# Precision_Arduino_Charlieplex_1_1.net
KiCad netlist of a schematic drawn in EAGLE
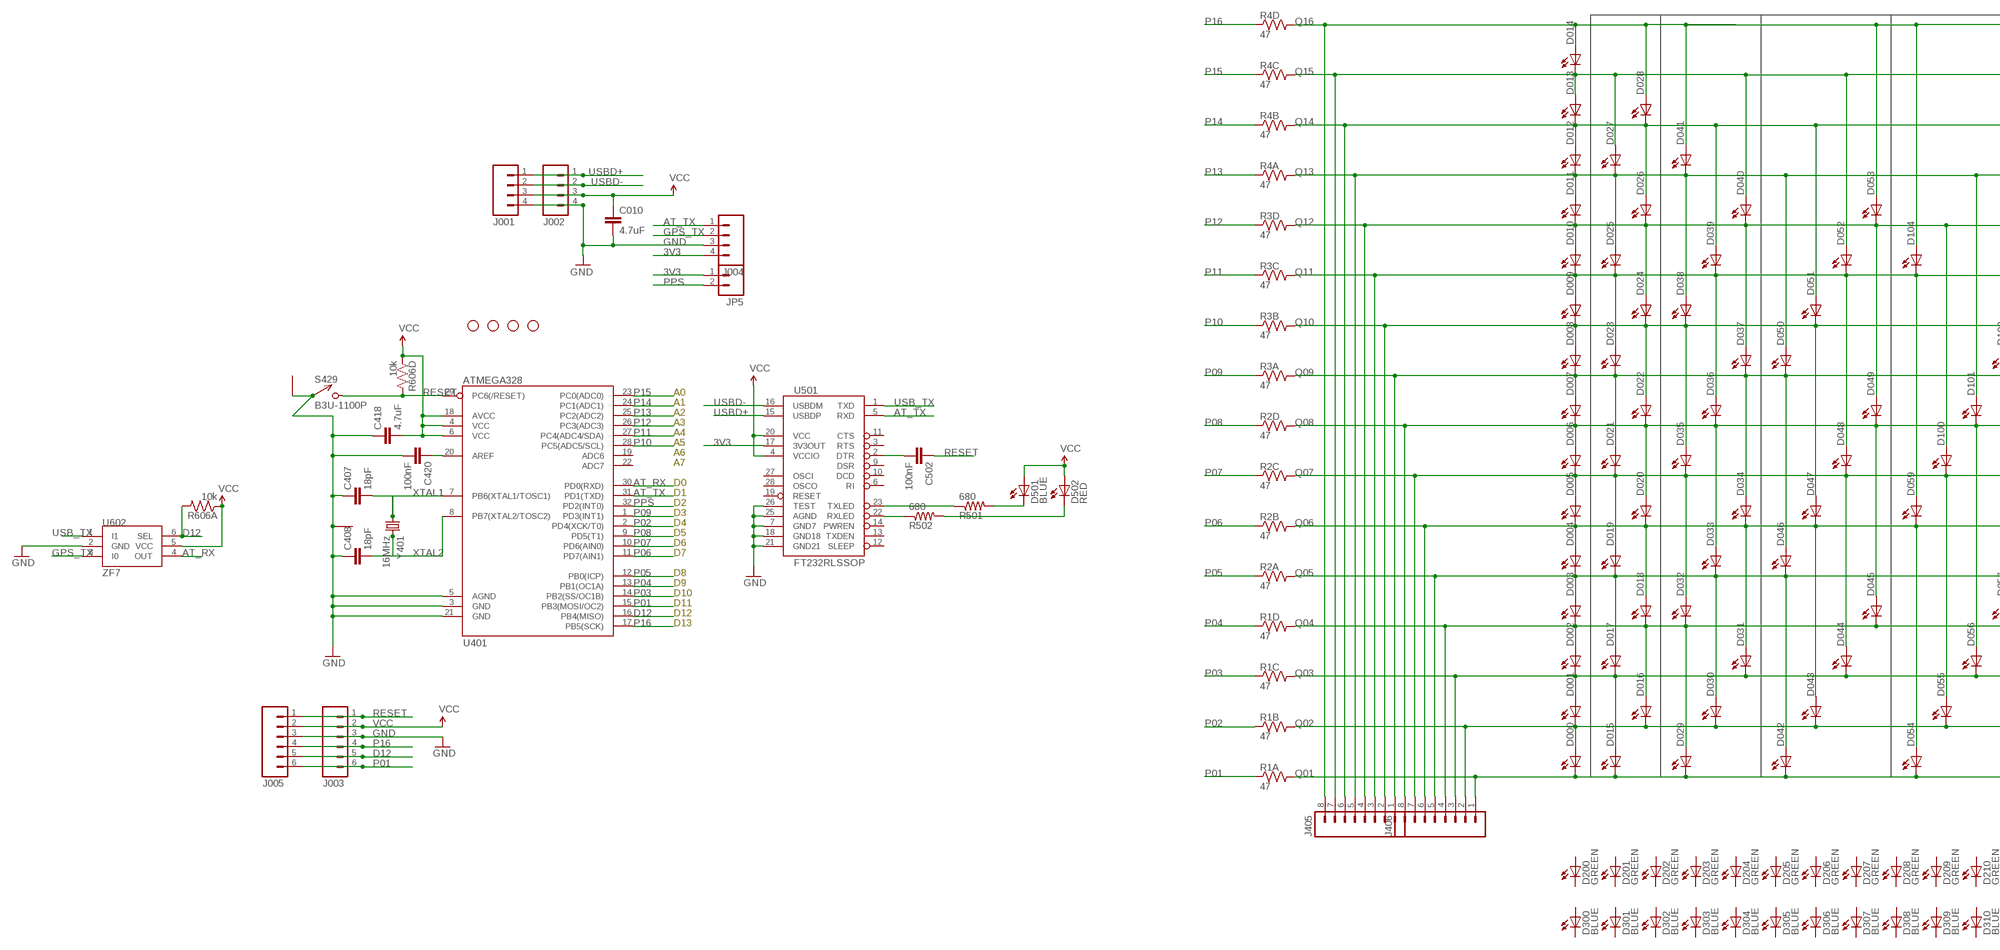
[diagram p0: schematic, sheet 1, part 1 of 2]
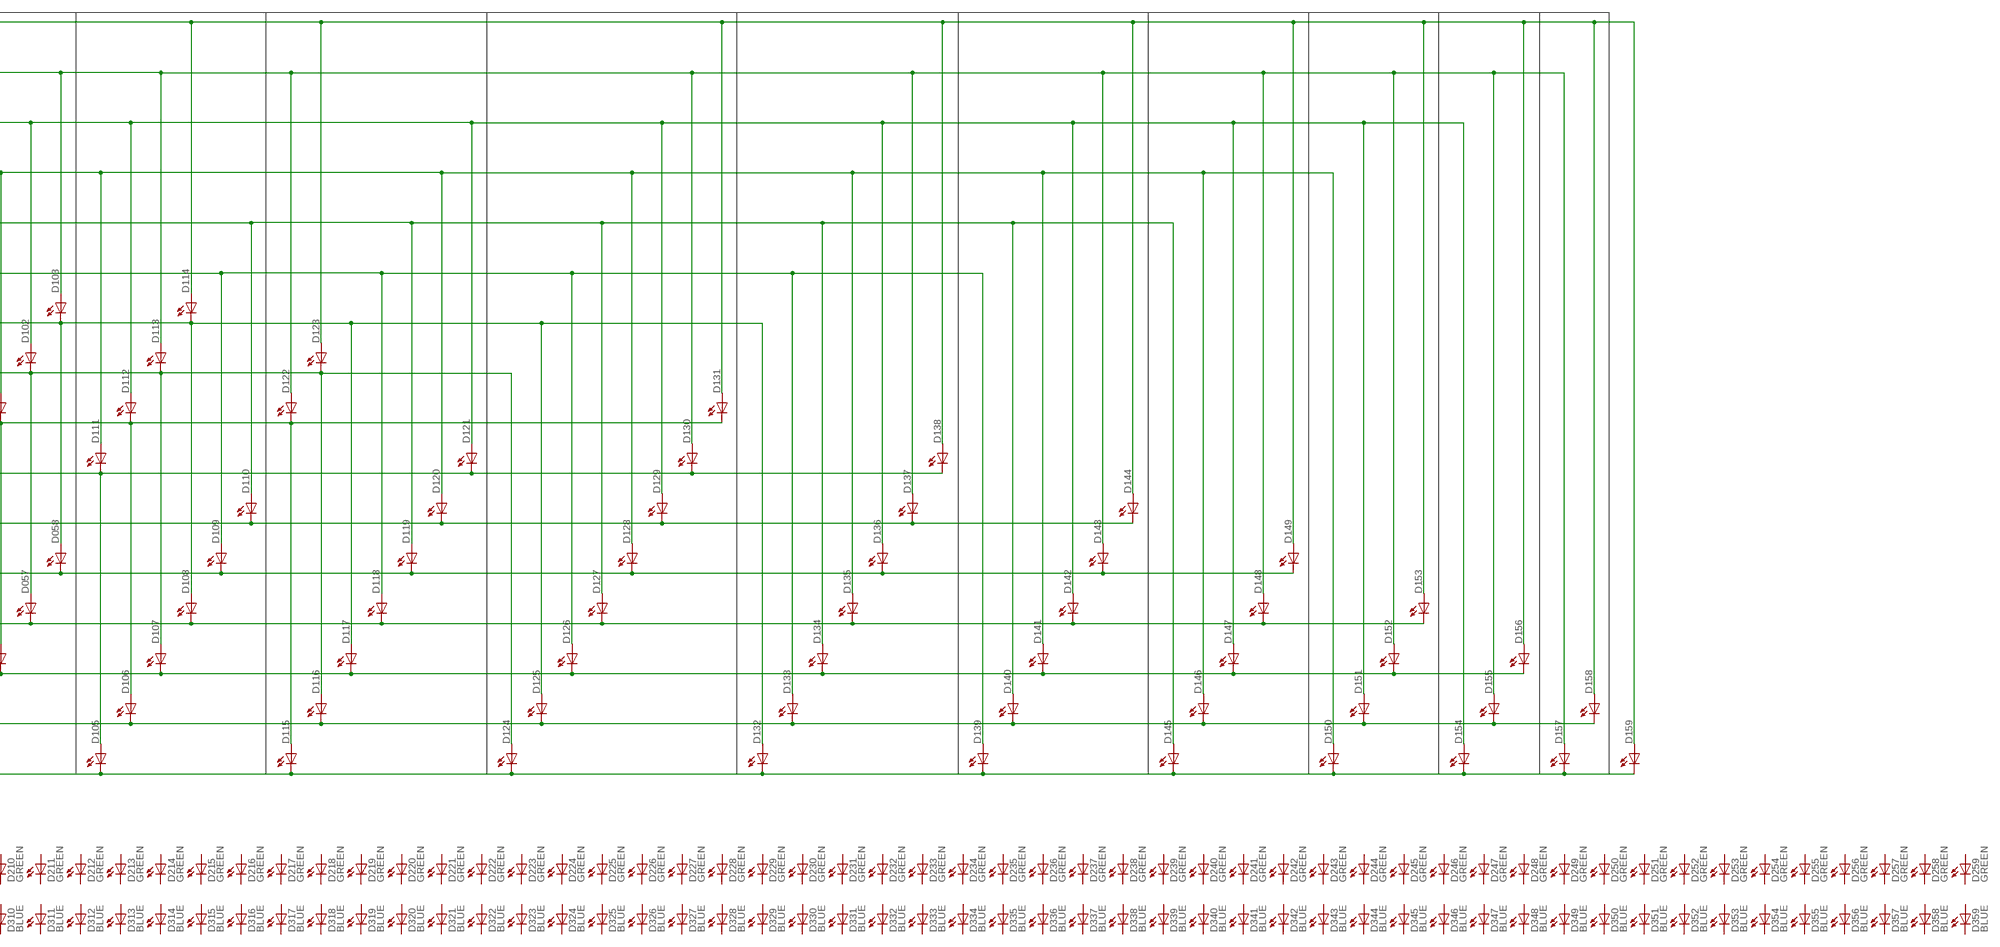
[diagram p1: schematic, sheet 1, part 2 of 2]

(export (version "E")
  (design (tool "Eeschema 10.0.6"))
  (components
    (comp (ref "C010")
      (value "4.7uF")
      (footprint "eagle-import:0603-CAP")
      (libsource (lib "eagle-import") (part "CAP0603-CAP"))
    )
    (comp (ref "C407")
      (value "18pF")
      (footprint "eagle-import:0603-CAP")
      (libsource (lib "eagle-import") (part "CAP0603-CAP"))
    )
    (comp (ref "C408")
      (value "18pF")
      (footprint "eagle-import:0603-CAP")
      (libsource (lib "eagle-import") (part "CAP0603-CAP"))
    )
    (comp (ref "C418")
      (value "4.7uF")
      (footprint "eagle-import:0603-CAP")
      (libsource (lib "eagle-import") (part "CAP0603-CAP"))
    )
    (comp (ref "C420")
      (value "100nF")
      (footprint "eagle-import:0603-CAP")
      (libsource (lib "eagle-import") (part "CAP0603-CAP"))
    )
    (comp (ref "C502")
      (value "100nF")
      (footprint "eagle-import:0603-CAP")
      (libsource (lib "eagle-import") (part "CAP0603-CAP"))
    )
    (comp (ref "D000")
      (value "RED")
      (footprint "eagle-import:LED-0603")
      (libsource (lib "eagle-import") (part "SparkFun-LED_LED0603"))
    )
    (comp (ref "D001")
      (value "RED")
      (footprint "eagle-import:LED-0603")
      (libsource (lib "eagle-import") (part "SparkFun-LED_LED0603"))
    )
    (comp (ref "D002")
      (value "RED")
      (footprint "eagle-import:LED-0603")
      (libsource (lib "eagle-import") (part "SparkFun-LED_LED0603"))
    )
    (comp (ref "D003")
      (value "RED")
      (footprint "eagle-import:LED-0603")
      (libsource (lib "eagle-import") (part "SparkFun-LED_LED0603"))
    )
    (comp (ref "D004")
      (value "RED")
      (footprint "eagle-import:LED-0603")
      (libsource (lib "eagle-import") (part "SparkFun-LED_LED0603"))
    )
    (comp (ref "D005")
      (value "RED")
      (footprint "eagle-import:LED-0603")
      (libsource (lib "eagle-import") (part "SparkFun-LED_LED0603"))
    )
    (comp (ref "D006")
      (value "RED")
      (footprint "eagle-import:LED-0603")
      (libsource (lib "eagle-import") (part "SparkFun-LED_LED0603"))
    )
    (comp (ref "D007")
      (value "RED")
      (footprint "eagle-import:LED-0603")
      (libsource (lib "eagle-import") (part "SparkFun-LED_LED0603"))
    )
    (comp (ref "D008")
      (value "RED")
      (footprint "eagle-import:LED-0603")
      (libsource (lib "eagle-import") (part "SparkFun-LED_LED0603"))
    )
    (comp (ref "D009")
      (value "RED")
      (footprint "eagle-import:LED-0603")
      (libsource (lib "eagle-import") (part "SparkFun-LED_LED0603"))
    )
    (comp (ref "D010")
      (value "RED")
      (footprint "eagle-import:LED-0603")
      (libsource (lib "eagle-import") (part "SparkFun-LED_LED0603"))
    )
    (comp (ref "D011")
      (value "RED")
      (footprint "eagle-import:LED-0603")
      (libsource (lib "eagle-import") (part "SparkFun-LED_LED0603"))
    )
    (comp (ref "D012")
      (value "RED")
      (footprint "eagle-import:LED-0603")
      (libsource (lib "eagle-import") (part "SparkFun-LED_LED0603"))
    )
    (comp (ref "D013")
      (value "RED")
      (footprint "eagle-import:LED-0603")
      (libsource (lib "eagle-import") (part "SparkFun-LED_LED0603"))
    )
    (comp (ref "D014")
      (value "RED")
      (footprint "eagle-import:LED-0603")
      (libsource (lib "eagle-import") (part "SparkFun-LED_LED0603"))
    )
    (comp (ref "D015")
      (value "RED")
      (footprint "eagle-import:LED-0603")
      (libsource (lib "eagle-import") (part "SparkFun-LED_LED0603"))
    )
    (comp (ref "D016")
      (value "RED")
      (footprint "eagle-import:LED-0603")
      (libsource (lib "eagle-import") (part "SparkFun-LED_LED0603"))
    )
    (comp (ref "D017")
      (value "RED")
      (footprint "eagle-import:LED-0603")
      (libsource (lib "eagle-import") (part "SparkFun-LED_LED0603"))
    )
    (comp (ref "D018")
      (value "RED")
      (footprint "eagle-import:LED-0603")
      (libsource (lib "eagle-import") (part "SparkFun-LED_LED0603"))
    )
    (comp (ref "D019")
      (value "RED")
      (footprint "eagle-import:LED-0603")
      (libsource (lib "eagle-import") (part "SparkFun-LED_LED0603"))
    )
    (comp (ref "D020")
      (value "RED")
      (footprint "eagle-import:LED-0603")
      (libsource (lib "eagle-import") (part "SparkFun-LED_LED0603"))
    )
    (comp (ref "D021")
      (value "RED")
      (footprint "eagle-import:LED-0603")
      (libsource (lib "eagle-import") (part "SparkFun-LED_LED0603"))
    )
    (comp (ref "D022")
      (value "RED")
      (footprint "eagle-import:LED-0603")
      (libsource (lib "eagle-import") (part "SparkFun-LED_LED0603"))
    )
    (comp (ref "D023")
      (value "RED")
      (footprint "eagle-import:LED-0603")
      (libsource (lib "eagle-import") (part "SparkFun-LED_LED0603"))
    )
    (comp (ref "D024")
      (value "RED")
      (footprint "eagle-import:LED-0603")
      (libsource (lib "eagle-import") (part "SparkFun-LED_LED0603"))
    )
    (comp (ref "D025")
      (value "RED")
      (footprint "eagle-import:LED-0603")
      (libsource (lib "eagle-import") (part "SparkFun-LED_LED0603"))
    )
    (comp (ref "D026")
      (value "RED")
      (footprint "eagle-import:LED-0603")
      (libsource (lib "eagle-import") (part "SparkFun-LED_LED0603"))
    )
    (comp (ref "D027")
      (value "RED")
      (footprint "eagle-import:LED-0603")
      (libsource (lib "eagle-import") (part "SparkFun-LED_LED0603"))
    )
    (comp (ref "D028")
      (value "RED")
      (footprint "eagle-import:LED-0603")
      (libsource (lib "eagle-import") (part "SparkFun-LED_LED0603"))
    )
    (comp (ref "D029")
      (value "RED")
      (footprint "eagle-import:LED-0603")
      (libsource (lib "eagle-import") (part "SparkFun-LED_LED0603"))
    )
    (comp (ref "D030")
      (value "RED")
      (footprint "eagle-import:LED-0603")
      (libsource (lib "eagle-import") (part "SparkFun-LED_LED0603"))
    )
    (comp (ref "D031")
      (value "RED")
      (footprint "eagle-import:LED-0603")
      (libsource (lib "eagle-import") (part "SparkFun-LED_LED0603"))
    )
    (comp (ref "D032")
      (value "RED")
      (footprint "eagle-import:LED-0603")
      (libsource (lib "eagle-import") (part "SparkFun-LED_LED0603"))
    )
    (comp (ref "D033")
      (value "RED")
      (footprint "eagle-import:LED-0603")
      (libsource (lib "eagle-import") (part "SparkFun-LED_LED0603"))
    )
    (comp (ref "D034")
      (value "RED")
      (footprint "eagle-import:LED-0603")
      (libsource (lib "eagle-import") (part "SparkFun-LED_LED0603"))
    )
    (comp (ref "D035")
      (value "RED")
      (footprint "eagle-import:LED-0603")
      (libsource (lib "eagle-import") (part "SparkFun-LED_LED0603"))
    )
    (comp (ref "D036")
      (value "RED")
      (footprint "eagle-import:LED-0603")
      (libsource (lib "eagle-import") (part "SparkFun-LED_LED0603"))
    )
    (comp (ref "D037")
      (value "RED")
      (footprint "eagle-import:LED-0603")
      (libsource (lib "eagle-import") (part "SparkFun-LED_LED0603"))
    )
    (comp (ref "D038")
      (value "RED")
      (footprint "eagle-import:LED-0603")
      (libsource (lib "eagle-import") (part "SparkFun-LED_LED0603"))
    )
    (comp (ref "D039")
      (value "RED")
      (footprint "eagle-import:LED-0603")
      (libsource (lib "eagle-import") (part "SparkFun-LED_LED0603"))
    )
    (comp (ref "D040")
      (value "RED")
      (footprint "eagle-import:LED-0603")
      (libsource (lib "eagle-import") (part "SparkFun-LED_LED0603"))
    )
    (comp (ref "D041")
      (value "RED")
      (footprint "eagle-import:LED-0603")
      (libsource (lib "eagle-import") (part "SparkFun-LED_LED0603"))
    )
    (comp (ref "D042")
      (value "RED")
      (footprint "eagle-import:LED-0603")
      (libsource (lib "eagle-import") (part "SparkFun-LED_LED0603"))
    )
    (comp (ref "D043")
      (value "RED")
      (footprint "eagle-import:LED-0603")
      (libsource (lib "eagle-import") (part "SparkFun-LED_LED0603"))
    )
    (comp (ref "D044")
      (value "RED")
      (footprint "eagle-import:LED-0603")
      (libsource (lib "eagle-import") (part "SparkFun-LED_LED0603"))
    )
    (comp (ref "D045")
      (value "RED")
      (footprint "eagle-import:LED-0603")
      (libsource (lib "eagle-import") (part "SparkFun-LED_LED0603"))
    )
    (comp (ref "D046")
      (value "RED")
      (footprint "eagle-import:LED-0603")
      (libsource (lib "eagle-import") (part "SparkFun-LED_LED0603"))
    )
    (comp (ref "D047")
      (value "RED")
      (footprint "eagle-import:LED-0603")
      (libsource (lib "eagle-import") (part "SparkFun-LED_LED0603"))
    )
    (comp (ref "D048")
      (value "RED")
      (footprint "eagle-import:LED-0603")
      (libsource (lib "eagle-import") (part "SparkFun-LED_LED0603"))
    )
    (comp (ref "D049")
      (value "RED")
      (footprint "eagle-import:LED-0603")
      (libsource (lib "eagle-import") (part "SparkFun-LED_LED0603"))
    )
    (comp (ref "D050")
      (value "RED")
      (footprint "eagle-import:LED-0603")
      (libsource (lib "eagle-import") (part "SparkFun-LED_LED0603"))
    )
    (comp (ref "D051")
      (value "RED")
      (footprint "eagle-import:LED-0603")
      (libsource (lib "eagle-import") (part "SparkFun-LED_LED0603"))
    )
    (comp (ref "D052")
      (value "RED")
      (footprint "eagle-import:LED-0603")
      (libsource (lib "eagle-import") (part "SparkFun-LED_LED0603"))
    )
    (comp (ref "D053")
      (value "RED")
      (footprint "eagle-import:LED-0603")
      (libsource (lib "eagle-import") (part "SparkFun-LED_LED0603"))
    )
    (comp (ref "D054")
      (value "RED")
      (footprint "eagle-import:LED-0603")
      (libsource (lib "eagle-import") (part "SparkFun-LED_LED0603"))
    )
    (comp (ref "D055")
      (value "RED")
      (footprint "eagle-import:LED-0603")
      (libsource (lib "eagle-import") (part "SparkFun-LED_LED0603"))
    )
    (comp (ref "D056")
      (value "RED")
      (footprint "eagle-import:LED-0603")
      (libsource (lib "eagle-import") (part "SparkFun-LED_LED0603"))
    )
    (comp (ref "D057")
      (value "RED")
      (footprint "eagle-import:LED-0603")
      (libsource (lib "eagle-import") (part "SparkFun-LED_LED0603"))
    )
    (comp (ref "D058")
      (value "RED")
      (footprint "eagle-import:LED-0603")
      (libsource (lib "eagle-import") (part "SparkFun-LED_LED0603"))
    )
    (comp (ref "D059")
      (value "RED")
      (footprint "eagle-import:LED-0603")
      (libsource (lib "eagle-import") (part "SparkFun-LED_LED0603"))
    )
    (comp (ref "D100")
      (value "YELLOW")
      (footprint "eagle-import:LED-0603")
      (libsource (lib "eagle-import") (part "SparkFun-LED_LED0603"))
    )
    (comp (ref "D101")
      (value "YELLOW")
      (footprint "eagle-import:LED-0603")
      (libsource (lib "eagle-import") (part "SparkFun-LED_LED0603"))
    )
    (comp (ref "D102")
      (value "YELLOW")
      (footprint "eagle-import:LED-0603")
      (libsource (lib "eagle-import") (part "SparkFun-LED_LED0603"))
    )
    (comp (ref "D103")
      (value "YELLOW")
      (footprint "eagle-import:LED-0603")
      (libsource (lib "eagle-import") (part "SparkFun-LED_LED0603"))
    )
    (comp (ref "D104")
      (value "YELLOW")
      (footprint "eagle-import:LED-0603")
      (libsource (lib "eagle-import") (part "SparkFun-LED_LED0603"))
    )
    (comp (ref "D105")
      (value "YELLOW")
      (footprint "eagle-import:LED-0603")
      (libsource (lib "eagle-import") (part "SparkFun-LED_LED0603"))
    )
    (comp (ref "D106")
      (value "YELLOW")
      (footprint "eagle-import:LED-0603")
      (libsource (lib "eagle-import") (part "SparkFun-LED_LED0603"))
    )
    (comp (ref "D107")
      (value "YELLOW")
      (footprint "eagle-import:LED-0603")
      (libsource (lib "eagle-import") (part "SparkFun-LED_LED0603"))
    )
    (comp (ref "D108")
      (value "YELLOW")
      (footprint "eagle-import:LED-0603")
      (libsource (lib "eagle-import") (part "SparkFun-LED_LED0603"))
    )
    (comp (ref "D109")
      (value "YELLOW")
      (footprint "eagle-import:LED-0603")
      (libsource (lib "eagle-import") (part "SparkFun-LED_LED0603"))
    )
    (comp (ref "D110")
      (value "YELLOW")
      (footprint "eagle-import:LED-0603")
      (libsource (lib "eagle-import") (part "SparkFun-LED_LED0603"))
    )
    (comp (ref "D111")
      (value "YELLOW")
      (footprint "eagle-import:LED-0603")
      (libsource (lib "eagle-import") (part "SparkFun-LED_LED0603"))
    )
    (comp (ref "D112")
      (value "YELLOW")
      (footprint "eagle-import:LED-0603")
      (libsource (lib "eagle-import") (part "SparkFun-LED_LED0603"))
    )
    (comp (ref "D113")
      (value "YELLOW")
      (footprint "eagle-import:LED-0603")
      (libsource (lib "eagle-import") (part "SparkFun-LED_LED0603"))
    )
    (comp (ref "D114")
      (value "YELLOW")
      (footprint "eagle-import:LED-0603")
      (libsource (lib "eagle-import") (part "SparkFun-LED_LED0603"))
    )
    (comp (ref "D115")
      (value "YELLOW")
      (footprint "eagle-import:LED-0603")
      (libsource (lib "eagle-import") (part "SparkFun-LED_LED0603"))
    )
    (comp (ref "D116")
      (value "YELLOW")
      (footprint "eagle-import:LED-0603")
      (libsource (lib "eagle-import") (part "SparkFun-LED_LED0603"))
    )
    (comp (ref "D117")
      (value "YELLOW")
      (footprint "eagle-import:LED-0603")
      (libsource (lib "eagle-import") (part "SparkFun-LED_LED0603"))
    )
    (comp (ref "D118")
      (value "YELLOW")
      (footprint "eagle-import:LED-0603")
      (libsource (lib "eagle-import") (part "SparkFun-LED_LED0603"))
    )
    (comp (ref "D119")
      (value "YELLOW")
      (footprint "eagle-import:LED-0603")
      (libsource (lib "eagle-import") (part "SparkFun-LED_LED0603"))
    )
    (comp (ref "D120")
      (value "YELLOW")
      (footprint "eagle-import:LED-0603")
      (libsource (lib "eagle-import") (part "SparkFun-LED_LED0603"))
    )
    (comp (ref "D121")
      (value "YELLOW")
      (footprint "eagle-import:LED-0603")
      (libsource (lib "eagle-import") (part "SparkFun-LED_LED0603"))
    )
    (comp (ref "D122")
      (value "YELLOW")
      (footprint "eagle-import:LED-0603")
      (libsource (lib "eagle-import") (part "SparkFun-LED_LED0603"))
    )
    (comp (ref "D123")
      (value "YELLOW")
      (footprint "eagle-import:LED-0603")
      (libsource (lib "eagle-import") (part "SparkFun-LED_LED0603"))
    )
    (comp (ref "D124")
      (value "YELLOW")
      (footprint "eagle-import:LED-0603")
      (libsource (lib "eagle-import") (part "SparkFun-LED_LED0603"))
    )
    (comp (ref "D125")
      (value "YELLOW")
      (footprint "eagle-import:LED-0603")
      (libsource (lib "eagle-import") (part "SparkFun-LED_LED0603"))
    )
    (comp (ref "D126")
      (value "YELLOW")
      (footprint "eagle-import:LED-0603")
      (libsource (lib "eagle-import") (part "SparkFun-LED_LED0603"))
    )
    (comp (ref "D127")
      (value "YELLOW")
      (footprint "eagle-import:LED-0603")
      (libsource (lib "eagle-import") (part "SparkFun-LED_LED0603"))
    )
    (comp (ref "D128")
      (value "YELLOW")
      (footprint "eagle-import:LED-0603")
      (libsource (lib "eagle-import") (part "SparkFun-LED_LED0603"))
    )
    (comp (ref "D129")
      (value "YELLOW")
      (footprint "eagle-import:LED-0603")
      (libsource (lib "eagle-import") (part "SparkFun-LED_LED0603"))
    )
    (comp (ref "D130")
      (value "YELLOW")
      (footprint "eagle-import:LED-0603")
      (libsource (lib "eagle-import") (part "SparkFun-LED_LED0603"))
    )
    (comp (ref "D131")
      (value "YELLOW")
      (footprint "eagle-import:LED-0603")
      (libsource (lib "eagle-import") (part "SparkFun-LED_LED0603"))
    )
    (comp (ref "D132")
      (value "YELLOW")
      (footprint "eagle-import:LED-0603")
      (libsource (lib "eagle-import") (part "SparkFun-LED_LED0603"))
    )
    (comp (ref "D133")
      (value "YELLOW")
      (footprint "eagle-import:LED-0603")
      (libsource (lib "eagle-import") (part "SparkFun-LED_LED0603"))
    )
    (comp (ref "D134")
      (value "YELLOW")
      (footprint "eagle-import:LED-0603")
      (libsource (lib "eagle-import") (part "SparkFun-LED_LED0603"))
    )
    (comp (ref "D135")
      (value "YELLOW")
      (footprint "eagle-import:LED-0603")
      (libsource (lib "eagle-import") (part "SparkFun-LED_LED0603"))
    )
    (comp (ref "D136")
      (value "YELLOW")
      (footprint "eagle-import:LED-0603")
      (libsource (lib "eagle-import") (part "SparkFun-LED_LED0603"))
    )
    (comp (ref "D137")
      (value "YELLOW")
      (footprint "eagle-import:LED-0603")
      (libsource (lib "eagle-import") (part "SparkFun-LED_LED0603"))
    )
    (comp (ref "D138")
      (value "YELLOW")
      (footprint "eagle-import:LED-0603")
      (libsource (lib "eagle-import") (part "SparkFun-LED_LED0603"))
    )
    (comp (ref "D139")
      (value "YELLOW")
      (footprint "eagle-import:LED-0603")
      (libsource (lib "eagle-import") (part "SparkFun-LED_LED0603"))
    )
    (comp (ref "D140")
      (value "YELLOW")
      (footprint "eagle-import:LED-0603")
      (libsource (lib "eagle-import") (part "SparkFun-LED_LED0603"))
    )
    (comp (ref "D141")
      (value "YELLOW")
      (footprint "eagle-import:LED-0603")
      (libsource (lib "eagle-import") (part "SparkFun-LED_LED0603"))
    )
    (comp (ref "D142")
      (value "YELLOW")
      (footprint "eagle-import:LED-0603")
      (libsource (lib "eagle-import") (part "SparkFun-LED_LED0603"))
    )
    (comp (ref "D143")
      (value "YELLOW")
      (footprint "eagle-import:LED-0603")
      (libsource (lib "eagle-import") (part "SparkFun-LED_LED0603"))
    )
    (comp (ref "D144")
      (value "YELLOW")
      (footprint "eagle-import:LED-0603")
      (libsource (lib "eagle-import") (part "SparkFun-LED_LED0603"))
    )
    (comp (ref "D145")
      (value "YELLOW")
      (footprint "eagle-import:LED-0603")
      (libsource (lib "eagle-import") (part "SparkFun-LED_LED0603"))
    )
    (comp (ref "D146")
      (value "YELLOW")
      (footprint "eagle-import:LED-0603")
      (libsource (lib "eagle-import") (part "SparkFun-LED_LED0603"))
    )
    (comp (ref "D147")
      (value "YELLOW")
      (footprint "eagle-import:LED-0603")
      (libsource (lib "eagle-import") (part "SparkFun-LED_LED0603"))
    )
    (comp (ref "D148")
      (value "YELLOW")
      (footprint "eagle-import:LED-0603")
      (libsource (lib "eagle-import") (part "SparkFun-LED_LED0603"))
    )
    (comp (ref "D149")
      (value "YELLOW")
      (footprint "eagle-import:LED-0603")
      (libsource (lib "eagle-import") (part "SparkFun-LED_LED0603"))
    )
    (comp (ref "D150")
      (value "YELLOW")
      (footprint "eagle-import:LED-0603")
      (libsource (lib "eagle-import") (part "SparkFun-LED_LED0603"))
    )
    (comp (ref "D151")
      (value "YELLOW")
      (footprint "eagle-import:LED-0603")
      (libsource (lib "eagle-import") (part "SparkFun-LED_LED0603"))
    )
    (comp (ref "D152")
      (value "YELLOW")
      (footprint "eagle-import:LED-0603")
      (libsource (lib "eagle-import") (part "SparkFun-LED_LED0603"))
    )
    (comp (ref "D153")
      (value "YELLOW")
      (footprint "eagle-import:LED-0603")
      (libsource (lib "eagle-import") (part "SparkFun-LED_LED0603"))
    )
    (comp (ref "D154")
      (value "YELLOW")
      (footprint "eagle-import:LED-0603")
      (libsource (lib "eagle-import") (part "SparkFun-LED_LED0603"))
    )
    (comp (ref "D155")
      (value "YELLOW")
      (footprint "eagle-import:LED-0603")
      (libsource (lib "eagle-import") (part "SparkFun-LED_LED0603"))
    )
    (comp (ref "D156")
      (value "YELLOW")
      (footprint "eagle-import:LED-0603")
      (libsource (lib "eagle-import") (part "SparkFun-LED_LED0603"))
    )
    (comp (ref "D157")
      (value "YELLOW")
      (footprint "eagle-import:LED-0603")
      (libsource (lib "eagle-import") (part "SparkFun-LED_LED0603"))
    )
    (comp (ref "D158")
      (value "YELLOW")
      (footprint "eagle-import:LED-0603")
      (libsource (lib "eagle-import") (part "SparkFun-LED_LED0603"))
    )
    (comp (ref "D159")
      (value "YELLOW")
      (footprint "eagle-import:LED-0603")
      (libsource (lib "eagle-import") (part "SparkFun-LED_LED0603"))
    )
    (comp (ref "D200")
      (value "GREEN")
      (footprint "eagle-import:LED-0603")
      (libsource (lib "eagle-import") (part "SparkFun-LED_LED0603"))
    )
    (comp (ref "D201")
      (value "GREEN")
      (footprint "eagle-import:LED-0603")
      (libsource (lib "eagle-import") (part "SparkFun-LED_LED0603"))
    )
    (comp (ref "D202")
      (value "GREEN")
      (footprint "eagle-import:LED-0603")
      (libsource (lib "eagle-import") (part "SparkFun-LED_LED0603"))
    )
    (comp (ref "D203")
      (value "GREEN")
      (footprint "eagle-import:LED-0603")
      (libsource (lib "eagle-import") (part "SparkFun-LED_LED0603"))
    )
    (comp (ref "D204")
      (value "GREEN")
      (footprint "eagle-import:LED-0603")
      (libsource (lib "eagle-import") (part "SparkFun-LED_LED0603"))
    )
    (comp (ref "D205")
      (value "GREEN")
      (footprint "eagle-import:LED-0603")
      (libsource (lib "eagle-import") (part "SparkFun-LED_LED0603"))
    )
    (comp (ref "D206")
      (value "GREEN")
      (footprint "eagle-import:LED-0603")
      (libsource (lib "eagle-import") (part "SparkFun-LED_LED0603"))
    )
    (comp (ref "D207")
      (value "GREEN")
      (footprint "eagle-import:LED-0603")
      (libsource (lib "eagle-import") (part "SparkFun-LED_LED0603"))
    )
    (comp (ref "D208")
      (value "GREEN")
      (footprint "eagle-import:LED-0603")
      (libsource (lib "eagle-import") (part "SparkFun-LED_LED0603"))
    )
    (comp (ref "D209")
      (value "GREEN")
      (footprint "eagle-import:LED-0603")
      (libsource (lib "eagle-import") (part "SparkFun-LED_LED0603"))
    )
    (comp (ref "D210")
      (value "GREEN")
      (footprint "eagle-import:LED-0603")
      (libsource (lib "eagle-import") (part "SparkFun-LED_LED0603"))
    )
    (comp (ref "D211")
      (value "GREEN")
      (footprint "eagle-import:LED-0603")
      (libsource (lib "eagle-import") (part "SparkFun-LED_LED0603"))
    )
    (comp (ref "D212")
      (value "GREEN")
      (footprint "eagle-import:LED-0603")
      (libsource (lib "eagle-import") (part "SparkFun-LED_LED0603"))
    )
    (comp (ref "D213")
      (value "GREEN")
      (footprint "eagle-import:LED-0603")
      (libsource (lib "eagle-import") (part "SparkFun-LED_LED0603"))
    )
    (comp (ref "D214")
      (value "GREEN")
      (footprint "eagle-import:LED-0603")
      (libsource (lib "eagle-import") (part "SparkFun-LED_LED0603"))
    )
    (comp (ref "D215")
      (value "GREEN")
      (footprint "eagle-import:LED-0603")
      (libsource (lib "eagle-import") (part "SparkFun-LED_LED0603"))
    )
    (comp (ref "D216")
      (value "GREEN")
      (footprint "eagle-import:LED-0603")
      (libsource (lib "eagle-import") (part "SparkFun-LED_LED0603"))
    )
    (comp (ref "D217")
      (value "GREEN")
      (footprint "eagle-import:LED-0603")
      (libsource (lib "eagle-import") (part "SparkFun-LED_LED0603"))
    )
    (comp (ref "D218")
      (value "GREEN")
      (footprint "eagle-import:LED-0603")
      (libsource (lib "eagle-import") (part "SparkFun-LED_LED0603"))
    )
    (comp (ref "D219")
      (value "GREEN")
      (footprint "eagle-import:LED-0603")
      (libsource (lib "eagle-import") (part "SparkFun-LED_LED0603"))
    )
    (comp (ref "D220")
      (value "GREEN")
      (footprint "eagle-import:LED-0603")
      (libsource (lib "eagle-import") (part "SparkFun-LED_LED0603"))
    )
    (comp (ref "D221")
      (value "GREEN")
      (footprint "eagle-import:LED-0603")
      (libsource (lib "eagle-import") (part "SparkFun-LED_LED0603"))
    )
    (comp (ref "D222")
      (value "GREEN")
      (footprint "eagle-import:LED-0603")
      (libsource (lib "eagle-import") (part "SparkFun-LED_LED0603"))
    )
    (comp (ref "D223")
      (value "GREEN")
      (footprint "eagle-import:LED-0603")
      (libsource (lib "eagle-import") (part "SparkFun-LED_LED0603"))
    )
    (comp (ref "D224")
      (value "GREEN")
      (footprint "eagle-import:LED-0603")
      (libsource (lib "eagle-import") (part "SparkFun-LED_LED0603"))
    )
    (comp (ref "D225")
      (value "GREEN")
      (footprint "eagle-import:LED-0603")
      (libsource (lib "eagle-import") (part "SparkFun-LED_LED0603"))
    )
    (comp (ref "D226")
      (value "GREEN")
      (footprint "eagle-import:LED-0603")
      (libsource (lib "eagle-import") (part "SparkFun-LED_LED0603"))
    )
    (comp (ref "D227")
      (value "GREEN")
      (footprint "eagle-import:LED-0603")
      (libsource (lib "eagle-import") (part "SparkFun-LED_LED0603"))
    )
    (comp (ref "D228")
      (value "GREEN")
      (footprint "eagle-import:LED-0603")
      (libsource (lib "eagle-import") (part "SparkFun-LED_LED0603"))
    )
    (comp (ref "D229")
      (value "GREEN")
      (footprint "eagle-import:LED-0603")
      (libsource (lib "eagle-import") (part "SparkFun-LED_LED0603"))
    )
    (comp (ref "D230")
      (value "GREEN")
      (footprint "eagle-import:LED-0603")
      (libsource (lib "eagle-import") (part "SparkFun-LED_LED0603"))
    )
    (comp (ref "D231")
      (value "GREEN")
      (footprint "eagle-import:LED-0603")
      (libsource (lib "eagle-import") (part "SparkFun-LED_LED0603"))
    )
    (comp (ref "D232")
      (value "GREEN")
      (footprint "eagle-import:LED-0603")
      (libsource (lib "eagle-import") (part "SparkFun-LED_LED0603"))
    )
    (comp (ref "D233")
      (value "GREEN")
      (footprint "eagle-import:LED-0603")
      (libsource (lib "eagle-import") (part "SparkFun-LED_LED0603"))
    )
    (comp (ref "D234")
      (value "GREEN")
      (footprint "eagle-import:LED-0603")
      (libsource (lib "eagle-import") (part "SparkFun-LED_LED0603"))
    )
    (comp (ref "D235")
      (value "GREEN")
      (footprint "eagle-import:LED-0603")
      (libsource (lib "eagle-import") (part "SparkFun-LED_LED0603"))
    )
    (comp (ref "D236")
      (value "GREEN")
      (footprint "eagle-import:LED-0603")
      (libsource (lib "eagle-import") (part "SparkFun-LED_LED0603"))
    )
    (comp (ref "D237")
      (value "GREEN")
      (footprint "eagle-import:LED-0603")
      (libsource (lib "eagle-import") (part "SparkFun-LED_LED0603"))
    )
    (comp (ref "D238")
      (value "GREEN")
      (footprint "eagle-import:LED-0603")
      (libsource (lib "eagle-import") (part "SparkFun-LED_LED0603"))
    )
    (comp (ref "D239")
      (value "GREEN")
      (footprint "eagle-import:LED-0603")
      (libsource (lib "eagle-import") (part "SparkFun-LED_LED0603"))
    )
    (comp (ref "D240")
      (value "GREEN")
      (footprint "eagle-import:LED-0603")
      (libsource (lib "eagle-import") (part "SparkFun-LED_LED0603"))
    )
    (comp (ref "D241")
      (value "GREEN")
      (footprint "eagle-import:LED-0603")
      (libsource (lib "eagle-import") (part "SparkFun-LED_LED0603"))
    )
    (comp (ref "D242")
      (value "GREEN")
      (footprint "eagle-import:LED-0603")
      (libsource (lib "eagle-import") (part "SparkFun-LED_LED0603"))
    )
    (comp (ref "D243")
      (value "GREEN")
      (footprint "eagle-import:LED-0603")
      (libsource (lib "eagle-import") (part "SparkFun-LED_LED0603"))
    )
    (comp (ref "D244")
      (value "GREEN")
      (footprint "eagle-import:LED-0603")
      (libsource (lib "eagle-import") (part "SparkFun-LED_LED0603"))
    )
    (comp (ref "D245")
      (value "GREEN")
      (footprint "eagle-import:LED-0603")
      (libsource (lib "eagle-import") (part "SparkFun-LED_LED0603"))
    )
    (comp (ref "D246")
      (value "GREEN")
      (footprint "eagle-import:LED-0603")
      (libsource (lib "eagle-import") (part "SparkFun-LED_LED0603"))
    )
    (comp (ref "D247")
      (value "GREEN")
      (footprint "eagle-import:LED-0603")
      (libsource (lib "eagle-import") (part "SparkFun-LED_LED0603"))
    )
    (comp (ref "D248")
      (value "GREEN")
      (footprint "eagle-import:LED-0603")
      (libsource (lib "eagle-import") (part "SparkFun-LED_LED0603"))
    )
    (comp (ref "D249")
      (value "GREEN")
      (footprint "eagle-import:LED-0603")
      (libsource (lib "eagle-import") (part "SparkFun-LED_LED0603"))
    )
    (comp (ref "D250")
      (value "GREEN")
      (footprint "eagle-import:LED-0603")
      (libsource (lib "eagle-import") (part "SparkFun-LED_LED0603"))
    )
    (comp (ref "D251")
      (value "GREEN")
      (footprint "eagle-import:LED-0603")
      (libsource (lib "eagle-import") (part "SparkFun-LED_LED0603"))
    )
    (comp (ref "D252")
      (value "GREEN")
      (footprint "eagle-import:LED-0603")
      (libsource (lib "eagle-import") (part "SparkFun-LED_LED0603"))
    )
    (comp (ref "D253")
      (value "GREEN")
      (footprint "eagle-import:LED-0603")
      (libsource (lib "eagle-import") (part "SparkFun-LED_LED0603"))
    )
    (comp (ref "D254")
      (value "GREEN")
      (footprint "eagle-import:LED-0603")
      (libsource (lib "eagle-import") (part "SparkFun-LED_LED0603"))
    )
    (comp (ref "D255")
      (value "GREEN")
      (footprint "eagle-import:LED-0603")
      (libsource (lib "eagle-import") (part "SparkFun-LED_LED0603"))
    )
    (comp (ref "D256")
      (value "GREEN")
      (footprint "eagle-import:LED-0603")
      (libsource (lib "eagle-import") (part "SparkFun-LED_LED0603"))
    )
    (comp (ref "D257")
      (value "GREEN")
      (footprint "eagle-import:LED-0603")
      (libsource (lib "eagle-import") (part "SparkFun-LED_LED0603"))
    )
    (comp (ref "D258")
      (value "GREEN")
      (footprint "eagle-import:LED-0603")
      (libsource (lib "eagle-import") (part "SparkFun-LED_LED0603"))
    )
    (comp (ref "D259")
      (value "GREEN")
      (footprint "eagle-import:LED-0603")
      (libsource (lib "eagle-import") (part "SparkFun-LED_LED0603"))
    )
    (comp (ref "D300")
      (value "BLUE")
      (footprint "eagle-import:LED-0603")
      (libsource (lib "eagle-import") (part "SparkFun-LED_LED0603"))
    )
    (comp (ref "D301")
      (value "BLUE")
      (footprint "eagle-import:LED-0603")
      (libsource (lib "eagle-import") (part "SparkFun-LED_LED0603"))
    )
    (comp (ref "D302")
      (value "BLUE")
      (footprint "eagle-import:LED-0603")
      (libsource (lib "eagle-import") (part "SparkFun-LED_LED0603"))
    )
    (comp (ref "D303")
      (value "BLUE")
      (footprint "eagle-import:LED-0603")
      (libsource (lib "eagle-import") (part "SparkFun-LED_LED0603"))
    )
    (comp (ref "D304")
      (value "BLUE")
      (footprint "eagle-import:LED-0603")
      (libsource (lib "eagle-import") (part "SparkFun-LED_LED0603"))
    )
    (comp (ref "D305")
      (value "BLUE")
      (footprint "eagle-import:LED-0603")
      (libsource (lib "eagle-import") (part "SparkFun-LED_LED0603"))
    )
    (comp (ref "D306")
      (value "BLUE")
      (footprint "eagle-import:LED-0603")
      (libsource (lib "eagle-import") (part "SparkFun-LED_LED0603"))
    )
    (comp (ref "D307")
      (value "BLUE")
      (footprint "eagle-import:LED-0603")
      (libsource (lib "eagle-import") (part "SparkFun-LED_LED0603"))
    )
    (comp (ref "D308")
      (value "BLUE")
      (footprint "eagle-import:LED-0603")
      (libsource (lib "eagle-import") (part "SparkFun-LED_LED0603"))
    )
    (comp (ref "D309")
      (value "BLUE")
      (footprint "eagle-import:LED-0603")
      (libsource (lib "eagle-import") (part "SparkFun-LED_LED0603"))
    )
    (comp (ref "D310")
      (value "BLUE")
      (footprint "eagle-import:LED-0603")
      (libsource (lib "eagle-import") (part "SparkFun-LED_LED0603"))
    )
    (comp (ref "D311")
      (value "BLUE")
      (footprint "eagle-import:LED-0603")
      (libsource (lib "eagle-import") (part "SparkFun-LED_LED0603"))
    )
    (comp (ref "D312")
      (value "BLUE")
      (footprint "eagle-import:LED-0603")
      (libsource (lib "eagle-import") (part "SparkFun-LED_LED0603"))
    )
    (comp (ref "D313")
      (value "BLUE")
      (footprint "eagle-import:LED-0603")
      (libsource (lib "eagle-import") (part "SparkFun-LED_LED0603"))
    )
    (comp (ref "D314")
      (value "BLUE")
      (footprint "eagle-import:LED-0603")
      (libsource (lib "eagle-import") (part "SparkFun-LED_LED0603"))
    )
    (comp (ref "D315")
      (value "BLUE")
      (footprint "eagle-import:LED-0603")
      (libsource (lib "eagle-import") (part "SparkFun-LED_LED0603"))
    )
    (comp (ref "D316")
      (value "BLUE")
      (footprint "eagle-import:LED-0603")
      (libsource (lib "eagle-import") (part "SparkFun-LED_LED0603"))
    )
    (comp (ref "D317")
      (value "BLUE")
      (footprint "eagle-import:LED-0603")
      (libsource (lib "eagle-import") (part "SparkFun-LED_LED0603"))
    )
    (comp (ref "D318")
      (value "BLUE")
      (footprint "eagle-import:LED-0603")
      (libsource (lib "eagle-import") (part "SparkFun-LED_LED0603"))
    )
    (comp (ref "D319")
      (value "BLUE")
      (footprint "eagle-import:LED-0603")
      (libsource (lib "eagle-import") (part "SparkFun-LED_LED0603"))
    )
    (comp (ref "D320")
      (value "BLUE")
      (footprint "eagle-import:LED-0603")
      (libsource (lib "eagle-import") (part "SparkFun-LED_LED0603"))
    )
    (comp (ref "D321")
      (value "BLUE")
      (footprint "eagle-import:LED-0603")
      (libsource (lib "eagle-import") (part "SparkFun-LED_LED0603"))
    )
    (comp (ref "D322")
      (value "BLUE")
      (footprint "eagle-import:LED-0603")
      (libsource (lib "eagle-import") (part "SparkFun-LED_LED0603"))
    )
    (comp (ref "D323")
      (value "BLUE")
      (footprint "eagle-import:LED-0603")
      (libsource (lib "eagle-import") (part "SparkFun-LED_LED0603"))
    )
    (comp (ref "D324")
      (value "BLUE")
      (footprint "eagle-import:LED-0603")
      (libsource (lib "eagle-import") (part "SparkFun-LED_LED0603"))
    )
    (comp (ref "D325")
      (value "BLUE")
      (footprint "eagle-import:LED-0603")
      (libsource (lib "eagle-import") (part "SparkFun-LED_LED0603"))
    )
    (comp (ref "D326")
      (value "BLUE")
      (footprint "eagle-import:LED-0603")
      (libsource (lib "eagle-import") (part "SparkFun-LED_LED0603"))
    )
    (comp (ref "D327")
      (value "BLUE")
      (footprint "eagle-import:LED-0603")
      (libsource (lib "eagle-import") (part "SparkFun-LED_LED0603"))
    )
    (comp (ref "D328")
      (value "BLUE")
      (footprint "eagle-import:LED-0603")
      (libsource (lib "eagle-import") (part "SparkFun-LED_LED0603"))
    )
    (comp (ref "D329")
      (value "BLUE")
      (footprint "eagle-import:LED-0603")
      (libsource (lib "eagle-import") (part "SparkFun-LED_LED0603"))
    )
    (comp (ref "D330")
      (value "BLUE")
      (footprint "eagle-import:LED-0603")
      (libsource (lib "eagle-import") (part "SparkFun-LED_LED0603"))
    )
    (comp (ref "D331")
      (value "BLUE")
      (footprint "eagle-import:LED-0603")
      (libsource (lib "eagle-import") (part "SparkFun-LED_LED0603"))
    )
    (comp (ref "D332")
      (value "BLUE")
      (footprint "eagle-import:LED-0603")
      (libsource (lib "eagle-import") (part "SparkFun-LED_LED0603"))
    )
    (comp (ref "D333")
      (value "BLUE")
      (footprint "eagle-import:LED-0603")
      (libsource (lib "eagle-import") (part "SparkFun-LED_LED0603"))
    )
    (comp (ref "D334")
      (value "BLUE")
      (footprint "eagle-import:LED-0603")
      (libsource (lib "eagle-import") (part "SparkFun-LED_LED0603"))
    )
    (comp (ref "D335")
      (value "BLUE")
      (footprint "eagle-import:LED-0603")
      (libsource (lib "eagle-import") (part "SparkFun-LED_LED0603"))
    )
    (comp (ref "D336")
      (value "BLUE")
      (footprint "eagle-import:LED-0603")
      (libsource (lib "eagle-import") (part "SparkFun-LED_LED0603"))
    )
    (comp (ref "D337")
      (value "BLUE")
      (footprint "eagle-import:LED-0603")
      (libsource (lib "eagle-import") (part "SparkFun-LED_LED0603"))
    )
    (comp (ref "D338")
      (value "BLUE")
      (footprint "eagle-import:LED-0603")
      (libsource (lib "eagle-import") (part "SparkFun-LED_LED0603"))
    )
    (comp (ref "D339")
      (value "BLUE")
      (footprint "eagle-import:LED-0603")
      (libsource (lib "eagle-import") (part "SparkFun-LED_LED0603"))
    )
    (comp (ref "D340")
      (value "BLUE")
      (footprint "eagle-import:LED-0603")
      (libsource (lib "eagle-import") (part "SparkFun-LED_LED0603"))
    )
    (comp (ref "D341")
      (value "BLUE")
      (footprint "eagle-import:LED-0603")
      (libsource (lib "eagle-import") (part "SparkFun-LED_LED0603"))
    )
    (comp (ref "D342")
      (value "BLUE")
      (footprint "eagle-import:LED-0603")
      (libsource (lib "eagle-import") (part "SparkFun-LED_LED0603"))
    )
    (comp (ref "D343")
      (value "BLUE")
      (footprint "eagle-import:LED-0603")
      (libsource (lib "eagle-import") (part "SparkFun-LED_LED0603"))
    )
    (comp (ref "D344")
      (value "BLUE")
      (footprint "eagle-import:LED-0603")
      (libsource (lib "eagle-import") (part "SparkFun-LED_LED0603"))
    )
    (comp (ref "D345")
      (value "BLUE")
      (footprint "eagle-import:LED-0603")
      (libsource (lib "eagle-import") (part "SparkFun-LED_LED0603"))
    )
    (comp (ref "D346")
      (value "BLUE")
      (footprint "eagle-import:LED-0603")
      (libsource (lib "eagle-import") (part "SparkFun-LED_LED0603"))
    )
    (comp (ref "D347")
      (value "BLUE")
      (footprint "eagle-import:LED-0603")
      (libsource (lib "eagle-import") (part "SparkFun-LED_LED0603"))
    )
    (comp (ref "D348")
      (value "BLUE")
      (footprint "eagle-import:LED-0603")
      (libsource (lib "eagle-import") (part "SparkFun-LED_LED0603"))
    )
    (comp (ref "D349")
      (value "BLUE")
      (footprint "eagle-import:LED-0603")
      (libsource (lib "eagle-import") (part "SparkFun-LED_LED0603"))
    )
    (comp (ref "D350")
      (value "BLUE")
      (footprint "eagle-import:LED-0603")
      (libsource (lib "eagle-import") (part "SparkFun-LED_LED0603"))
    )
    (comp (ref "D351")
      (value "BLUE")
      (footprint "eagle-import:LED-0603")
      (libsource (lib "eagle-import") (part "SparkFun-LED_LED0603"))
    )
    (comp (ref "D352")
      (value "BLUE")
      (footprint "eagle-import:LED-0603")
      (libsource (lib "eagle-import") (part "SparkFun-LED_LED0603"))
    )
    (comp (ref "D353")
      (value "BLUE")
      (footprint "eagle-import:LED-0603")
      (libsource (lib "eagle-import") (part "SparkFun-LED_LED0603"))
    )
    (comp (ref "D354")
      (value "BLUE")
      (footprint "eagle-import:LED-0603")
      (libsource (lib "eagle-import") (part "SparkFun-LED_LED0603"))
    )
    (comp (ref "D355")
      (value "BLUE")
      (footprint "eagle-import:LED-0603")
      (libsource (lib "eagle-import") (part "SparkFun-LED_LED0603"))
    )
    (comp (ref "D356")
      (value "BLUE")
      (footprint "eagle-import:LED-0603")
      (libsource (lib "eagle-import") (part "SparkFun-LED_LED0603"))
    )
    (comp (ref "D357")
      (value "BLUE")
      (footprint "eagle-import:LED-0603")
      (libsource (lib "eagle-import") (part "SparkFun-LED_LED0603"))
    )
    (comp (ref "D358")
      (value "BLUE")
      (footprint "eagle-import:LED-0603")
      (libsource (lib "eagle-import") (part "SparkFun-LED_LED0603"))
    )
    (comp (ref "D359")
      (value "BLUE")
      (footprint "eagle-import:LED-0603")
      (libsource (lib "eagle-import") (part "SparkFun-LED_LED0603"))
    )
    (comp (ref "D501")
      (value "BLUE")
      (footprint "eagle-import:LED-0603")
      (libsource (lib "eagle-import") (part "LED0603"))
    )
    (comp (ref "D502")
      (value "RED")
      (footprint "eagle-import:LED-0603")
      (libsource (lib "eagle-import") (part "LED0603"))
    )
    (comp (ref "J001")
      (value "M04PTH")
      (footprint "eagle-import:1X04")
      (libsource (lib "eagle-import") (part "M04PTH"))
    )
    (comp (ref "J002")
      (value "M04PTH")
      (footprint "eagle-import:1X04")
      (libsource (lib "eagle-import") (part "M04PTH"))
    )
    (comp (ref "J003")
      (value "M06SIP")
      (footprint "eagle-import:1X06")
      (libsource (lib "eagle-import") (part "M06SIP"))
    )
    (comp (ref "J004")
      (value "M04PTH")
      (footprint "eagle-import:1X04")
      (libsource (lib "eagle-import") (part "M04PTH"))
    )
    (comp (ref "J005")
      (value "M06SIP")
      (footprint "eagle-import:1X06")
      (libsource (lib "eagle-import") (part "M06SIP"))
    )
    (comp (ref "J405")
      (value "M081X08")
      (footprint "eagle-import:1X08")
      (libsource (lib "eagle-import") (part "M081X08"))
    )
    (comp (ref "J406")
      (value "M081X08")
      (footprint "eagle-import:1X08")
      (libsource (lib "eagle-import") (part "M081X08"))
    )
    (comp (ref "JP1")
      (value "STAND-OFF")
      (footprint "eagle-import:STAND-OFF")
      (libsource (lib "eagle-import") (part "STAND-OFF"))
    )
    (comp (ref "JP2")
      (value "STAND-OFF")
      (footprint "eagle-import:STAND-OFF")
      (libsource (lib "eagle-import") (part "STAND-OFF"))
    )
    (comp (ref "JP3")
      (value "STAND-OFF")
      (footprint "eagle-import:STAND-OFF")
      (libsource (lib "eagle-import") (part "STAND-OFF"))
    )
    (comp (ref "JP4")
      (value "STAND-OFF")
      (footprint "eagle-import:STAND-OFF")
      (libsource (lib "eagle-import") (part "STAND-OFF"))
    )
    (comp (ref "JP5")
      (value "M02PTH")
      (footprint "eagle-import:1X02")
      (libsource (lib "eagle-import") (part "M02PTH"))
    )
    (comp (ref "R1")
      (value "47")
      (footprint "eagle-import:CRA04")
      (fields (field (name "DIGIKEY") "CRA4S847CT-ND"))
      (libsource (lib "eagle-import") (part "RP404"))
    )
    (comp (ref "R2")
      (value "47")
      (footprint "eagle-import:CRA04")
      (fields (field (name "DIGIKEY") "CRA4S847CT-ND"))
      (libsource (lib "eagle-import") (part "RP404"))
    )
    (comp (ref "R3")
      (value "47")
      (footprint "eagle-import:CRA04")
      (fields (field (name "DIGIKEY") "CRA4S847CT-ND"))
      (libsource (lib "eagle-import") (part "RP404"))
    )
    (comp (ref "R4")
      (value "47")
      (footprint "eagle-import:CRA04")
      (fields (field (name "DIGIKEY") "CRA4S847CT-ND"))
      (libsource (lib "eagle-import") (part "RP404"))
    )
    (comp (ref "R501")
      (value "680")
      (footprint "eagle-import:0603-RES")
      (libsource (lib "eagle-import") (part "RESISTOR0603-RES"))
    )
    (comp (ref "R502")
      (value "680")
      (footprint "eagle-import:0603-RES")
      (libsource (lib "eagle-import") (part "RESISTOR0603-RES"))
    )
    (comp (ref "R606")
      (value "10k")
      (footprint "eagle-import:CRA04")
      (fields (field (name "DIGIKEY") "CRA4S810KCT-ND"))
      (libsource (lib "eagle-import") (part "RP404"))
    )
    (comp (ref "S429")
      (value "B3U-1100P")
      (footprint "eagle-import:B3U-1100P")
      (fields (field (name "DIGIKEY") "SW1021CT-ND"))
      (libsource (lib "eagle-import") (part "B3U-1100P"))
    )
    (comp (ref "U401")
      (value "ATMEGA328")
      (footprint "eagle-import:TQFP32-08")
      (libsource (lib "eagle-import") (part "ATMEGA168"))
    )
    (comp (ref "U501")
      (value "FT232RLSSOP")
      (footprint "eagle-import:SSOP28DB")
      (libsource (lib "eagle-import") (part "FT232RLSSOP"))
    )
    (comp (ref "U602")
      (value "ZF7")
      (footprint "eagle-import:SC-70-6")
      (libsource (lib "eagle-import") (part "NC7SZ157"))
    )
    (comp (ref "Y401")
      (value "16MHz")
      (footprint "eagle-import:CRYSTAL_SMD")
      (fields (field (name "DIGIKEY") "887-1319-1-ND"))
      (libsource (lib "eagle-import") (part "TSX-3225"))
    )
  )
  (nets
    (net (code "1") (name "/3V3") (class "Default")
      (node (ref "J004") (pin "4") (pinfunction "4_4") (pintype "passive"))
      (node (ref "JP5") (pin "1") (pinfunction "1_1") (pintype "passive"))
      (node (ref "U501") (pin "17") (pinfunction "3V3OUT_17") (pintype "output"))
    )
    (net (code "2") (name "/AT_RX") (class "Default")
      (node (ref "U401") (pin "30") (pinfunction "PD0(RXD)_30") (pintype "bidirectional"))
      (node (ref "U602") (pin "4") (pinfunction "OUT_4") (pintype "bidirectional"))
    )
    (net (code "3") (name "/AT_TX") (class "Default")
      (node (ref "J004") (pin "1") (pinfunction "1_1") (pintype "passive"))
      (node (ref "U401") (pin "31") (pinfunction "PD1(TXD)_31") (pintype "bidirectional"))
      (node (ref "U501") (pin "5") (pinfunction "RXD_5") (pintype "input"))
    )
    (net (code "4") (name "/D12") (class "Default")
      (node (ref "J003") (pin "5") (pinfunction "5_5") (pintype "passive"))
      (node (ref "J005") (pin "5") (pinfunction "5_5") (pintype "passive"))
      (node (ref "R606") (pin "8") (pinfunction "2_8") (pintype "passive"))
      (node (ref "U401") (pin "16") (pinfunction "PB4(MISO)_16") (pintype "bidirectional"))
      (node (ref "U602") (pin "6") (pinfunction "SEL_6") (pintype "bidirectional"))
    )
    (net (code "5") (name "/GPS_TX") (class "Default")
      (node (ref "J004") (pin "2") (pinfunction "2_2") (pintype "passive"))
      (node (ref "U602") (pin "3") (pinfunction "I0_3") (pintype "bidirectional"))
    )
    (net (code "6") (name "/P01") (class "Default")
      (node (ref "J003") (pin "6") (pinfunction "6_6") (pintype "passive"))
      (node (ref "J005") (pin "6") (pinfunction "6_6") (pintype "passive"))
      (node (ref "R1") (pin "1") (pinfunction "1_1") (pintype "passive"))
      (node (ref "U401") (pin "15") (pinfunction "PB3(MOSI/OC2)_15") (pintype "bidirectional"))
    )
    (net (code "7") (name "/P02") (class "Default")
      (node (ref "R1") (pin "2") (pinfunction "1_2") (pintype "passive"))
      (node (ref "U401") (pin "2") (pinfunction "PD4(XCK/T0)_2") (pintype "bidirectional"))
    )
    (net (code "8") (name "/P03") (class "Default")
      (node (ref "R1") (pin "3") (pinfunction "1_3") (pintype "passive"))
      (node (ref "U401") (pin "14") (pinfunction "PB2(SS/OC1B)_14") (pintype "bidirectional"))
    )
    (net (code "9") (name "/P04") (class "Default")
      (node (ref "R1") (pin "4") (pinfunction "1_4") (pintype "passive"))
      (node (ref "U401") (pin "13") (pinfunction "PB1(OC1A)_13") (pintype "bidirectional"))
    )
    (net (code "10") (name "/P05") (class "Default")
      (node (ref "R2") (pin "1") (pinfunction "1_1") (pintype "passive"))
      (node (ref "U401") (pin "12") (pinfunction "PB0(ICP)_12") (pintype "bidirectional"))
    )
    (net (code "11") (name "/P06") (class "Default")
      (node (ref "R2") (pin "2") (pinfunction "1_2") (pintype "passive"))
      (node (ref "U401") (pin "11") (pinfunction "PD7(AIN1)_11") (pintype "bidirectional"))
    )
    (net (code "12") (name "/P07") (class "Default")
      (node (ref "R2") (pin "3") (pinfunction "1_3") (pintype "passive"))
      (node (ref "U401") (pin "10") (pinfunction "PD6(AIN0)_10") (pintype "bidirectional"))
    )
    (net (code "13") (name "/P08") (class "Default")
      (node (ref "R2") (pin "4") (pinfunction "1_4") (pintype "passive"))
      (node (ref "U401") (pin "9") (pinfunction "PD5(T1)_9") (pintype "bidirectional"))
    )
    (net (code "14") (name "/P09") (class "Default")
      (node (ref "R3") (pin "1") (pinfunction "1_1") (pintype "passive"))
      (node (ref "U401") (pin "1") (pinfunction "PD3(INT1)_1") (pintype "bidirectional"))
    )
    (net (code "15") (name "/P10") (class "Default")
      (node (ref "R3") (pin "2") (pinfunction "1_2") (pintype "passive"))
      (node (ref "U401") (pin "28") (pinfunction "PC5(ADC5/SCL)_28") (pintype "bidirectional"))
    )
    (net (code "16") (name "/P11") (class "Default")
      (node (ref "R3") (pin "3") (pinfunction "1_3") (pintype "passive"))
      (node (ref "U401") (pin "27") (pinfunction "PC4(ADC4/SDA)_27") (pintype "bidirectional"))
    )
    (net (code "17") (name "/P12") (class "Default")
      (node (ref "R3") (pin "4") (pinfunction "1_4") (pintype "passive"))
      (node (ref "U401") (pin "26") (pinfunction "PC3(ADC3)_26") (pintype "bidirectional"))
    )
    (net (code "18") (name "/P13") (class "Default")
      (node (ref "R4") (pin "1") (pinfunction "1_1") (pintype "passive"))
      (node (ref "U401") (pin "25") (pinfunction "PC2(ADC2)_25") (pintype "bidirectional"))
    )
    (net (code "19") (name "/P14") (class "Default")
      (node (ref "R4") (pin "2") (pinfunction "1_2") (pintype "passive"))
      (node (ref "U401") (pin "24") (pinfunction "PC1(ADC1)_24") (pintype "bidirectional"))
    )
    (net (code "20") (name "/P15") (class "Default")
      (node (ref "R4") (pin "3") (pinfunction "1_3") (pintype "passive"))
      (node (ref "U401") (pin "23") (pinfunction "PC0(ADC0)_23") (pintype "bidirectional"))
    )
    (net (code "21") (name "/P16") (class "Default")
      (node (ref "J003") (pin "4") (pinfunction "4_4") (pintype "passive"))
      (node (ref "J005") (pin "4") (pinfunction "4_4") (pintype "passive"))
      (node (ref "R4") (pin "4") (pinfunction "1_4") (pintype "passive"))
      (node (ref "U401") (pin "17") (pinfunction "PB5(SCK)_17") (pintype "bidirectional"))
    )
    (net (code "22") (name "/PPS") (class "Default")
      (node (ref "JP5") (pin "2") (pinfunction "2_2") (pintype "passive"))
      (node (ref "U401") (pin "32") (pinfunction "PD2(INT0)_32") (pintype "bidirectional"))
    )
    (net (code "23") (name "/Q01") (class "Default")
      (node (ref "D000") (pin "C") (pinfunction "C_C") (pintype "passive"))
      (node (ref "D015") (pin "C") (pinfunction "C_C") (pintype "passive"))
      (node (ref "D029") (pin "C") (pinfunction "C_C") (pintype "passive"))
      (node (ref "D042") (pin "C") (pinfunction "C_C") (pintype "passive"))
      (node (ref "D054") (pin "C") (pinfunction "C_C") (pintype "passive"))
      (node (ref "D105") (pin "C") (pinfunction "C_C") (pintype "passive"))
      (node (ref "D115") (pin "C") (pinfunction "C_C") (pintype "passive"))
      (node (ref "D124") (pin "C") (pinfunction "C_C") (pintype "passive"))
      (node (ref "D132") (pin "C") (pinfunction "C_C") (pintype "passive"))
      (node (ref "D139") (pin "C") (pinfunction "C_C") (pintype "passive"))
      (node (ref "D145") (pin "C") (pinfunction "C_C") (pintype "passive"))
      (node (ref "D150") (pin "C") (pinfunction "C_C") (pintype "passive"))
      (node (ref "D154") (pin "C") (pinfunction "C_C") (pintype "passive"))
      (node (ref "D157") (pin "C") (pinfunction "C_C") (pintype "passive"))
      (node (ref "D159") (pin "C") (pinfunction "C_C") (pintype "passive"))
      (node (ref "J406") (pin "1") (pinfunction "1_1") (pintype "passive"))
      (node (ref "R1") (pin "8") (pinfunction "2_8") (pintype "passive"))
    )
    (net (code "24") (name "/Q02") (class "Default")
      (node (ref "D000") (pin "A") (pinfunction "A_A") (pintype "passive"))
      (node (ref "D001") (pin "C") (pinfunction "C_C") (pintype "passive"))
      (node (ref "D016") (pin "C") (pinfunction "C_C") (pintype "passive"))
      (node (ref "D030") (pin "C") (pinfunction "C_C") (pintype "passive"))
      (node (ref "D043") (pin "C") (pinfunction "C_C") (pintype "passive"))
      (node (ref "D055") (pin "C") (pinfunction "C_C") (pintype "passive"))
      (node (ref "D106") (pin "C") (pinfunction "C_C") (pintype "passive"))
      (node (ref "D116") (pin "C") (pinfunction "C_C") (pintype "passive"))
      (node (ref "D125") (pin "C") (pinfunction "C_C") (pintype "passive"))
      (node (ref "D133") (pin "C") (pinfunction "C_C") (pintype "passive"))
      (node (ref "D140") (pin "C") (pinfunction "C_C") (pintype "passive"))
      (node (ref "D146") (pin "C") (pinfunction "C_C") (pintype "passive"))
      (node (ref "D151") (pin "C") (pinfunction "C_C") (pintype "passive"))
      (node (ref "D155") (pin "C") (pinfunction "C_C") (pintype "passive"))
      (node (ref "D158") (pin "C") (pinfunction "C_C") (pintype "passive"))
      (node (ref "J406") (pin "2") (pinfunction "2_2") (pintype "passive"))
      (node (ref "R1") (pin "7") (pinfunction "2_7") (pintype "passive"))
    )
    (net (code "25") (name "/Q03") (class "Default")
      (node (ref "D001") (pin "A") (pinfunction "A_A") (pintype "passive"))
      (node (ref "D002") (pin "C") (pinfunction "C_C") (pintype "passive"))
      (node (ref "D015") (pin "A") (pinfunction "A_A") (pintype "passive"))
      (node (ref "D017") (pin "C") (pinfunction "C_C") (pintype "passive"))
      (node (ref "D031") (pin "C") (pinfunction "C_C") (pintype "passive"))
      (node (ref "D044") (pin "C") (pinfunction "C_C") (pintype "passive"))
      (node (ref "D056") (pin "C") (pinfunction "C_C") (pintype "passive"))
      (node (ref "D107") (pin "C") (pinfunction "C_C") (pintype "passive"))
      (node (ref "D117") (pin "C") (pinfunction "C_C") (pintype "passive"))
      (node (ref "D126") (pin "C") (pinfunction "C_C") (pintype "passive"))
      (node (ref "D134") (pin "C") (pinfunction "C_C") (pintype "passive"))
      (node (ref "D141") (pin "C") (pinfunction "C_C") (pintype "passive"))
      (node (ref "D147") (pin "C") (pinfunction "C_C") (pintype "passive"))
      (node (ref "D152") (pin "C") (pinfunction "C_C") (pintype "passive"))
      (node (ref "D156") (pin "C") (pinfunction "C_C") (pintype "passive"))
      (node (ref "J406") (pin "3") (pinfunction "3_3") (pintype "passive"))
      (node (ref "R1") (pin "6") (pinfunction "2_6") (pintype "passive"))
    )
    (net (code "26") (name "/Q04") (class "Default")
      (node (ref "D002") (pin "A") (pinfunction "A_A") (pintype "passive"))
      (node (ref "D003") (pin "C") (pinfunction "C_C") (pintype "passive"))
      (node (ref "D016") (pin "A") (pinfunction "A_A") (pintype "passive"))
      (node (ref "D018") (pin "C") (pinfunction "C_C") (pintype "passive"))
      (node (ref "D029") (pin "A") (pinfunction "A_A") (pintype "passive"))
      (node (ref "D032") (pin "C") (pinfunction "C_C") (pintype "passive"))
      (node (ref "D045") (pin "C") (pinfunction "C_C") (pintype "passive"))
      (node (ref "D057") (pin "C") (pinfunction "C_C") (pintype "passive"))
      (node (ref "D108") (pin "C") (pinfunction "C_C") (pintype "passive"))
      (node (ref "D118") (pin "C") (pinfunction "C_C") (pintype "passive"))
      (node (ref "D127") (pin "C") (pinfunction "C_C") (pintype "passive"))
      (node (ref "D135") (pin "C") (pinfunction "C_C") (pintype "passive"))
      (node (ref "D142") (pin "C") (pinfunction "C_C") (pintype "passive"))
      (node (ref "D148") (pin "C") (pinfunction "C_C") (pintype "passive"))
      (node (ref "D153") (pin "C") (pinfunction "C_C") (pintype "passive"))
      (node (ref "J406") (pin "4") (pinfunction "4_4") (pintype "passive"))
      (node (ref "R1") (pin "5") (pinfunction "2_5") (pintype "passive"))
    )
    (net (code "27") (name "/Q05") (class "Default")
      (node (ref "D003") (pin "A") (pinfunction "A_A") (pintype "passive"))
      (node (ref "D004") (pin "C") (pinfunction "C_C") (pintype "passive"))
      (node (ref "D017") (pin "A") (pinfunction "A_A") (pintype "passive"))
      (node (ref "D019") (pin "C") (pinfunction "C_C") (pintype "passive"))
      (node (ref "D030") (pin "A") (pinfunction "A_A") (pintype "passive"))
      (node (ref "D033") (pin "C") (pinfunction "C_C") (pintype "passive"))
      (node (ref "D042") (pin "A") (pinfunction "A_A") (pintype "passive"))
      (node (ref "D046") (pin "C") (pinfunction "C_C") (pintype "passive"))
      (node (ref "D058") (pin "C") (pinfunction "C_C") (pintype "passive"))
      (node (ref "D109") (pin "C") (pinfunction "C_C") (pintype "passive"))
      (node (ref "D119") (pin "C") (pinfunction "C_C") (pintype "passive"))
      (node (ref "D128") (pin "C") (pinfunction "C_C") (pintype "passive"))
      (node (ref "D136") (pin "C") (pinfunction "C_C") (pintype "passive"))
      (node (ref "D143") (pin "C") (pinfunction "C_C") (pintype "passive"))
      (node (ref "D149") (pin "C") (pinfunction "C_C") (pintype "passive"))
      (node (ref "J406") (pin "5") (pinfunction "5_5") (pintype "passive"))
      (node (ref "R2") (pin "8") (pinfunction "2_8") (pintype "passive"))
    )
    (net (code "28") (name "/Q06") (class "Default")
      (node (ref "D004") (pin "A") (pinfunction "A_A") (pintype "passive"))
      (node (ref "D005") (pin "C") (pinfunction "C_C") (pintype "passive"))
      (node (ref "D018") (pin "A") (pinfunction "A_A") (pintype "passive"))
      (node (ref "D020") (pin "C") (pinfunction "C_C") (pintype "passive"))
      (node (ref "D031") (pin "A") (pinfunction "A_A") (pintype "passive"))
      (node (ref "D034") (pin "C") (pinfunction "C_C") (pintype "passive"))
      (node (ref "D043") (pin "A") (pinfunction "A_A") (pintype "passive"))
      (node (ref "D047") (pin "C") (pinfunction "C_C") (pintype "passive"))
      (node (ref "D054") (pin "A") (pinfunction "A_A") (pintype "passive"))
      (node (ref "D059") (pin "C") (pinfunction "C_C") (pintype "passive"))
      (node (ref "D110") (pin "C") (pinfunction "C_C") (pintype "passive"))
      (node (ref "D120") (pin "C") (pinfunction "C_C") (pintype "passive"))
      (node (ref "D129") (pin "C") (pinfunction "C_C") (pintype "passive"))
      (node (ref "D137") (pin "C") (pinfunction "C_C") (pintype "passive"))
      (node (ref "D144") (pin "C") (pinfunction "C_C") (pintype "passive"))
      (node (ref "J406") (pin "6") (pinfunction "6_6") (pintype "passive"))
      (node (ref "R2") (pin "7") (pinfunction "2_7") (pintype "passive"))
    )
    (net (code "29") (name "/Q07") (class "Default")
      (node (ref "D005") (pin "A") (pinfunction "A_A") (pintype "passive"))
      (node (ref "D006") (pin "C") (pinfunction "C_C") (pintype "passive"))
      (node (ref "D019") (pin "A") (pinfunction "A_A") (pintype "passive"))
      (node (ref "D021") (pin "C") (pinfunction "C_C") (pintype "passive"))
      (node (ref "D032") (pin "A") (pinfunction "A_A") (pintype "passive"))
      (node (ref "D035") (pin "C") (pinfunction "C_C") (pintype "passive"))
      (node (ref "D044") (pin "A") (pinfunction "A_A") (pintype "passive"))
      (node (ref "D048") (pin "C") (pinfunction "C_C") (pintype "passive"))
      (node (ref "D055") (pin "A") (pinfunction "A_A") (pintype "passive"))
      (node (ref "D100") (pin "C") (pinfunction "C_C") (pintype "passive"))
      (node (ref "D105") (pin "A") (pinfunction "A_A") (pintype "passive"))
      (node (ref "D111") (pin "C") (pinfunction "C_C") (pintype "passive"))
      (node (ref "D121") (pin "C") (pinfunction "C_C") (pintype "passive"))
      (node (ref "D130") (pin "C") (pinfunction "C_C") (pintype "passive"))
      (node (ref "D138") (pin "C") (pinfunction "C_C") (pintype "passive"))
      (node (ref "J406") (pin "7") (pinfunction "7_7") (pintype "passive"))
      (node (ref "R2") (pin "6") (pinfunction "2_6") (pintype "passive"))
    )
    (net (code "30") (name "/Q08") (class "Default")
      (node (ref "D006") (pin "A") (pinfunction "A_A") (pintype "passive"))
      (node (ref "D007") (pin "C") (pinfunction "C_C") (pintype "passive"))
      (node (ref "D020") (pin "A") (pinfunction "A_A") (pintype "passive"))
      (node (ref "D022") (pin "C") (pinfunction "C_C") (pintype "passive"))
      (node (ref "D033") (pin "A") (pinfunction "A_A") (pintype "passive"))
      (node (ref "D036") (pin "C") (pinfunction "C_C") (pintype "passive"))
      (node (ref "D045") (pin "A") (pinfunction "A_A") (pintype "passive"))
      (node (ref "D049") (pin "C") (pinfunction "C_C") (pintype "passive"))
      (node (ref "D056") (pin "A") (pinfunction "A_A") (pintype "passive"))
      (node (ref "D101") (pin "C") (pinfunction "C_C") (pintype "passive"))
      (node (ref "D106") (pin "A") (pinfunction "A_A") (pintype "passive"))
      (node (ref "D112") (pin "C") (pinfunction "C_C") (pintype "passive"))
      (node (ref "D115") (pin "A") (pinfunction "A_A") (pintype "passive"))
      (node (ref "D122") (pin "C") (pinfunction "C_C") (pintype "passive"))
      (node (ref "D131") (pin "C") (pinfunction "C_C") (pintype "passive"))
      (node (ref "J406") (pin "8") (pinfunction "8_8") (pintype "passive"))
      (node (ref "R2") (pin "5") (pinfunction "2_5") (pintype "passive"))
    )
    (net (code "31") (name "/Q09") (class "Default")
      (node (ref "D007") (pin "A") (pinfunction "A_A") (pintype "passive"))
      (node (ref "D008") (pin "C") (pinfunction "C_C") (pintype "passive"))
      (node (ref "D021") (pin "A") (pinfunction "A_A") (pintype "passive"))
      (node (ref "D023") (pin "C") (pinfunction "C_C") (pintype "passive"))
      (node (ref "D034") (pin "A") (pinfunction "A_A") (pintype "passive"))
      (node (ref "D037") (pin "C") (pinfunction "C_C") (pintype "passive"))
      (node (ref "D046") (pin "A") (pinfunction "A_A") (pintype "passive"))
      (node (ref "D050") (pin "C") (pinfunction "C_C") (pintype "passive"))
      (node (ref "D057") (pin "A") (pinfunction "A_A") (pintype "passive"))
      (node (ref "D102") (pin "C") (pinfunction "C_C") (pintype "passive"))
      (node (ref "D107") (pin "A") (pinfunction "A_A") (pintype "passive"))
      (node (ref "D113") (pin "C") (pinfunction "C_C") (pintype "passive"))
      (node (ref "D116") (pin "A") (pinfunction "A_A") (pintype "passive"))
      (node (ref "D123") (pin "C") (pinfunction "C_C") (pintype "passive"))
      (node (ref "D124") (pin "A") (pinfunction "A_A") (pintype "passive"))
      (node (ref "J405") (pin "1") (pinfunction "1_1") (pintype "passive"))
      (node (ref "R3") (pin "8") (pinfunction "2_8") (pintype "passive"))
    )
    (net (code "32") (name "/Q10") (class "Default")
      (node (ref "D008") (pin "A") (pinfunction "A_A") (pintype "passive"))
      (node (ref "D009") (pin "C") (pinfunction "C_C") (pintype "passive"))
      (node (ref "D022") (pin "A") (pinfunction "A_A") (pintype "passive"))
      (node (ref "D024") (pin "C") (pinfunction "C_C") (pintype "passive"))
      (node (ref "D035") (pin "A") (pinfunction "A_A") (pintype "passive"))
      (node (ref "D038") (pin "C") (pinfunction "C_C") (pintype "passive"))
      (node (ref "D047") (pin "A") (pinfunction "A_A") (pintype "passive"))
      (node (ref "D051") (pin "C") (pinfunction "C_C") (pintype "passive"))
      (node (ref "D058") (pin "A") (pinfunction "A_A") (pintype "passive"))
      (node (ref "D103") (pin "C") (pinfunction "C_C") (pintype "passive"))
      (node (ref "D108") (pin "A") (pinfunction "A_A") (pintype "passive"))
      (node (ref "D114") (pin "C") (pinfunction "C_C") (pintype "passive"))
      (node (ref "D117") (pin "A") (pinfunction "A_A") (pintype "passive"))
      (node (ref "D125") (pin "A") (pinfunction "A_A") (pintype "passive"))
      (node (ref "D132") (pin "A") (pinfunction "A_A") (pintype "passive"))
      (node (ref "J405") (pin "2") (pinfunction "2_2") (pintype "passive"))
      (node (ref "R3") (pin "7") (pinfunction "2_7") (pintype "passive"))
    )
    (net (code "33") (name "/Q11") (class "Default")
      (node (ref "D009") (pin "A") (pinfunction "A_A") (pintype "passive"))
      (node (ref "D010") (pin "C") (pinfunction "C_C") (pintype "passive"))
      (node (ref "D023") (pin "A") (pinfunction "A_A") (pintype "passive"))
      (node (ref "D025") (pin "C") (pinfunction "C_C") (pintype "passive"))
      (node (ref "D036") (pin "A") (pinfunction "A_A") (pintype "passive"))
      (node (ref "D039") (pin "C") (pinfunction "C_C") (pintype "passive"))
      (node (ref "D048") (pin "A") (pinfunction "A_A") (pintype "passive"))
      (node (ref "D052") (pin "C") (pinfunction "C_C") (pintype "passive"))
      (node (ref "D059") (pin "A") (pinfunction "A_A") (pintype "passive"))
      (node (ref "D104") (pin "C") (pinfunction "C_C") (pintype "passive"))
      (node (ref "D109") (pin "A") (pinfunction "A_A") (pintype "passive"))
      (node (ref "D118") (pin "A") (pinfunction "A_A") (pintype "passive"))
      (node (ref "D126") (pin "A") (pinfunction "A_A") (pintype "passive"))
      (node (ref "D133") (pin "A") (pinfunction "A_A") (pintype "passive"))
      (node (ref "D139") (pin "A") (pinfunction "A_A") (pintype "passive"))
      (node (ref "J405") (pin "3") (pinfunction "3_3") (pintype "passive"))
      (node (ref "R3") (pin "6") (pinfunction "2_6") (pintype "passive"))
    )
    (net (code "34") (name "/Q12") (class "Default")
      (node (ref "D010") (pin "A") (pinfunction "A_A") (pintype "passive"))
      (node (ref "D011") (pin "C") (pinfunction "C_C") (pintype "passive"))
      (node (ref "D024") (pin "A") (pinfunction "A_A") (pintype "passive"))
      (node (ref "D026") (pin "C") (pinfunction "C_C") (pintype "passive"))
      (node (ref "D037") (pin "A") (pinfunction "A_A") (pintype "passive"))
      (node (ref "D040") (pin "C") (pinfunction "C_C") (pintype "passive"))
      (node (ref "D049") (pin "A") (pinfunction "A_A") (pintype "passive"))
      (node (ref "D053") (pin "C") (pinfunction "C_C") (pintype "passive"))
      (node (ref "D100") (pin "A") (pinfunction "A_A") (pintype "passive"))
      (node (ref "D110") (pin "A") (pinfunction "A_A") (pintype "passive"))
      (node (ref "D119") (pin "A") (pinfunction "A_A") (pintype "passive"))
      (node (ref "D127") (pin "A") (pinfunction "A_A") (pintype "passive"))
      (node (ref "D134") (pin "A") (pinfunction "A_A") (pintype "passive"))
      (node (ref "D140") (pin "A") (pinfunction "A_A") (pintype "passive"))
      (node (ref "D145") (pin "A") (pinfunction "A_A") (pintype "passive"))
      (node (ref "J405") (pin "4") (pinfunction "4_4") (pintype "passive"))
      (node (ref "R3") (pin "5") (pinfunction "2_5") (pintype "passive"))
    )
    (net (code "35") (name "/Q13") (class "Default")
      (node (ref "D011") (pin "A") (pinfunction "A_A") (pintype "passive"))
      (node (ref "D012") (pin "C") (pinfunction "C_C") (pintype "passive"))
      (node (ref "D025") (pin "A") (pinfunction "A_A") (pintype "passive"))
      (node (ref "D027") (pin "C") (pinfunction "C_C") (pintype "passive"))
      (node (ref "D038") (pin "A") (pinfunction "A_A") (pintype "passive"))
      (node (ref "D041") (pin "C") (pinfunction "C_C") (pintype "passive"))
      (node (ref "D050") (pin "A") (pinfunction "A_A") (pintype "passive"))
      (node (ref "D101") (pin "A") (pinfunction "A_A") (pintype "passive"))
      (node (ref "D111") (pin "A") (pinfunction "A_A") (pintype "passive"))
      (node (ref "D120") (pin "A") (pinfunction "A_A") (pintype "passive"))
      (node (ref "D128") (pin "A") (pinfunction "A_A") (pintype "passive"))
      (node (ref "D135") (pin "A") (pinfunction "A_A") (pintype "passive"))
      (node (ref "D141") (pin "A") (pinfunction "A_A") (pintype "passive"))
      (node (ref "D146") (pin "A") (pinfunction "A_A") (pintype "passive"))
      (node (ref "D150") (pin "A") (pinfunction "A_A") (pintype "passive"))
      (node (ref "J405") (pin "5") (pinfunction "5_5") (pintype "passive"))
      (node (ref "R4") (pin "8") (pinfunction "2_8") (pintype "passive"))
    )
    (net (code "36") (name "/Q14") (class "Default")
      (node (ref "D012") (pin "A") (pinfunction "A_A") (pintype "passive"))
      (node (ref "D013") (pin "C") (pinfunction "C_C") (pintype "passive"))
      (node (ref "D026") (pin "A") (pinfunction "A_A") (pintype "passive"))
      (node (ref "D028") (pin "C") (pinfunction "C_C") (pintype "passive"))
      (node (ref "D039") (pin "A") (pinfunction "A_A") (pintype "passive"))
      (node (ref "D051") (pin "A") (pinfunction "A_A") (pintype "passive"))
      (node (ref "D102") (pin "A") (pinfunction "A_A") (pintype "passive"))
      (node (ref "D112") (pin "A") (pinfunction "A_A") (pintype "passive"))
      (node (ref "D121") (pin "A") (pinfunction "A_A") (pintype "passive"))
      (node (ref "D129") (pin "A") (pinfunction "A_A") (pintype "passive"))
      (node (ref "D136") (pin "A") (pinfunction "A_A") (pintype "passive"))
      (node (ref "D142") (pin "A") (pinfunction "A_A") (pintype "passive"))
      (node (ref "D147") (pin "A") (pinfunction "A_A") (pintype "passive"))
      (node (ref "D151") (pin "A") (pinfunction "A_A") (pintype "passive"))
      (node (ref "D154") (pin "A") (pinfunction "A_A") (pintype "passive"))
      (node (ref "J405") (pin "6") (pinfunction "6_6") (pintype "passive"))
      (node (ref "R4") (pin "7") (pinfunction "2_7") (pintype "passive"))
    )
    (net (code "37") (name "/Q15") (class "Default")
      (node (ref "D013") (pin "A") (pinfunction "A_A") (pintype "passive"))
      (node (ref "D014") (pin "C") (pinfunction "C_C") (pintype "passive"))
      (node (ref "D027") (pin "A") (pinfunction "A_A") (pintype "passive"))
      (node (ref "D040") (pin "A") (pinfunction "A_A") (pintype "passive"))
      (node (ref "D052") (pin "A") (pinfunction "A_A") (pintype "passive"))
      (node (ref "D103") (pin "A") (pinfunction "A_A") (pintype "passive"))
      (node (ref "D113") (pin "A") (pinfunction "A_A") (pintype "passive"))
      (node (ref "D122") (pin "A") (pinfunction "A_A") (pintype "passive"))
      (node (ref "D130") (pin "A") (pinfunction "A_A") (pintype "passive"))
      (node (ref "D137") (pin "A") (pinfunction "A_A") (pintype "passive"))
      (node (ref "D143") (pin "A") (pinfunction "A_A") (pintype "passive"))
      (node (ref "D148") (pin "A") (pinfunction "A_A") (pintype "passive"))
      (node (ref "D152") (pin "A") (pinfunction "A_A") (pintype "passive"))
      (node (ref "D155") (pin "A") (pinfunction "A_A") (pintype "passive"))
      (node (ref "D157") (pin "A") (pinfunction "A_A") (pintype "passive"))
      (node (ref "J405") (pin "7") (pinfunction "7_7") (pintype "passive"))
      (node (ref "R4") (pin "6") (pinfunction "2_6") (pintype "passive"))
    )
    (net (code "38") (name "/Q16") (class "Default")
      (node (ref "D014") (pin "A") (pinfunction "A_A") (pintype "passive"))
      (node (ref "D028") (pin "A") (pinfunction "A_A") (pintype "passive"))
      (node (ref "D041") (pin "A") (pinfunction "A_A") (pintype "passive"))
      (node (ref "D053") (pin "A") (pinfunction "A_A") (pintype "passive"))
      (node (ref "D104") (pin "A") (pinfunction "A_A") (pintype "passive"))
      (node (ref "D114") (pin "A") (pinfunction "A_A") (pintype "passive"))
      (node (ref "D123") (pin "A") (pinfunction "A_A") (pintype "passive"))
      (node (ref "D131") (pin "A") (pinfunction "A_A") (pintype "passive"))
      (node (ref "D138") (pin "A") (pinfunction "A_A") (pintype "passive"))
      (node (ref "D144") (pin "A") (pinfunction "A_A") (pintype "passive"))
      (node (ref "D149") (pin "A") (pinfunction "A_A") (pintype "passive"))
      (node (ref "D153") (pin "A") (pinfunction "A_A") (pintype "passive"))
      (node (ref "D156") (pin "A") (pinfunction "A_A") (pintype "passive"))
      (node (ref "D158") (pin "A") (pinfunction "A_A") (pintype "passive"))
      (node (ref "D159") (pin "A") (pinfunction "A_A") (pintype "passive"))
      (node (ref "J405") (pin "8") (pinfunction "8_8") (pintype "passive"))
      (node (ref "R4") (pin "5") (pinfunction "2_5") (pintype "passive"))
    )
    (net (code "39") (name "/RESET") (class "Default")
      (node (ref "C502") (pin "1") (pinfunction "1_1") (pintype "passive"))
      (node (ref "J003") (pin "1") (pinfunction "1_1") (pintype "passive"))
      (node (ref "J005") (pin "1") (pinfunction "1_1") (pintype "passive"))
      (node (ref "R606") (pin "5") (pinfunction "2_5") (pintype "passive"))
      (node (ref "S429") (pin "P$2") (pinfunction "2_P$2") (pintype "bidirectional"))
      (node (ref "U401") (pin "29") (pinfunction "PC6(/RESET)_29") (pintype "bidirectional"))
    )
    (net (code "40") (name "/USBD+") (class "Default")
      (node (ref "J001") (pin "1") (pinfunction "1_1") (pintype "passive"))
      (node (ref "J002") (pin "1") (pinfunction "1_1") (pintype "passive"))
      (node (ref "U501") (pin "15") (pinfunction "USBDP_15") (pintype "bidirectional"))
    )
    (net (code "41") (name "/USBD-") (class "Default")
      (node (ref "J001") (pin "2") (pinfunction "2_2") (pintype "passive"))
      (node (ref "J002") (pin "2") (pinfunction "2_2") (pintype "passive"))
      (node (ref "U501") (pin "16") (pinfunction "USBDM_16") (pintype "bidirectional"))
    )
    (net (code "42") (name "/USB_TX") (class "Default")
      (node (ref "U501") (pin "1") (pinfunction "TXD_1") (pintype "output"))
      (node (ref "U602") (pin "1") (pinfunction "I1_1") (pintype "bidirectional"))
    )
    (net (code "43") (name "/XTAL1") (class "Default")
      (node (ref "C407") (pin "2") (pinfunction "2_2") (pintype "passive"))
      (node (ref "U401") (pin "7") (pinfunction "PB6(XTAL1/TOSC1)_7") (pintype "bidirectional"))
      (node (ref "Y401") (pin "1") (pinfunction "1_1") (pintype "passive"))
    )
    (net (code "44") (name "/XTAL2") (class "Default")
      (node (ref "C408") (pin "2") (pinfunction "2_2") (pintype "passive"))
      (node (ref "U401") (pin "8") (pinfunction "PB7(XTAL2/TOSC2)_8") (pintype "bidirectional"))
      (node (ref "Y401") (pin "3") (pinfunction "2_3") (pintype "passive"))
    )
    (net (code "45") (name "GND") (class "Default")
      (node (ref "C010") (pin "2") (pinfunction "2_2") (pintype "passive"))
      (node (ref "C407") (pin "1") (pinfunction "1_1") (pintype "passive"))
      (node (ref "C408") (pin "1") (pinfunction "1_1") (pintype "passive"))
      (node (ref "C418") (pin "1") (pinfunction "1_1") (pintype "passive"))
      (node (ref "C420") (pin "2") (pinfunction "2_2") (pintype "passive"))
      (node (ref "J001") (pin "4") (pinfunction "4_4") (pintype "passive"))
      (node (ref "J002") (pin "4") (pinfunction "4_4") (pintype "passive"))
      (node (ref "J003") (pin "3") (pinfunction "3_3") (pintype "passive"))
      (node (ref "J004") (pin "3") (pinfunction "3_3") (pintype "passive"))
      (node (ref "J005") (pin "3") (pinfunction "3_3") (pintype "passive"))
      (node (ref "S429") (pin "P$1") (pinfunction "1_P$1") (pintype "bidirectional"))
      (node (ref "S429") (pin "P$3") (pinfunction "1_P$3") (pintype "bidirectional"))
      (node (ref "U401") (pin "21") (pinfunction "GND_21") (pintype "bidirectional"))
      (node (ref "U401") (pin "3") (pinfunction "GND_3") (pintype "bidirectional"))
      (node (ref "U401") (pin "5") (pinfunction "AGND_5") (pintype "bidirectional"))
      (node (ref "U501") (pin "18") (pinfunction "GND18_18") (pintype "power_in"))
      (node (ref "U501") (pin "21") (pinfunction "GND21_21") (pintype "power_in"))
      (node (ref "U501") (pin "25") (pinfunction "AGND_25") (pintype "power_in"))
      (node (ref "U501") (pin "26") (pinfunction "TEST_26") (pintype "input"))
      (node (ref "U501") (pin "7") (pinfunction "GND7_7") (pintype "power_in"))
      (node (ref "U602") (pin "2") (pinfunction "GND_2") (pintype "bidirectional"))
      (node (ref "Y401") (pin "2") (pinfunction "1_2") (pintype "bidirectional"))
      (node (ref "Y401") (pin "4") (pinfunction "1_4") (pintype "bidirectional"))
    )
    (net (code "46") (name "Net-(D501-PadC)") (class "Default")
      (node (ref "D501") (pin "C") (pinfunction "C_C") (pintype "passive"))
      (node (ref "R501") (pin "2") (pinfunction "2_2") (pintype "passive"))
    )
    (net (code "47") (name "Net-(D502-PadC)") (class "Default")
      (node (ref "D502") (pin "C") (pinfunction "C_C") (pintype "passive"))
      (node (ref "R502") (pin "2") (pinfunction "2_2") (pintype "passive"))
    )
    (net (code "48") (name "Net-(U401-AREF)") (class "Default")
      (node (ref "C420") (pin "1") (pinfunction "1_1") (pintype "passive"))
      (node (ref "U401") (pin "20") (pinfunction "AREF_20") (pintype "bidirectional"))
    )
    (net (code "49") (name "Net-(U501-DTR)") (class "Default")
      (node (ref "C502") (pin "2") (pinfunction "2_2") (pintype "passive"))
      (node (ref "U501") (pin "2") (pinfunction "DTR_2") (pintype "output"))
    )
    (net (code "50") (name "Net-(U501-RXLED)") (class "Default")
      (node (ref "R502") (pin "1") (pinfunction "1_1") (pintype "passive"))
      (node (ref "U501") (pin "22") (pinfunction "RXLED_22") (pintype "input"))
    )
    (net (code "51") (name "Net-(U501-TXLED)") (class "Default")
      (node (ref "R501") (pin "1") (pinfunction "1_1") (pintype "passive"))
      (node (ref "U501") (pin "23") (pinfunction "TXLED_23") (pintype "input"))
    )
    (net (code "52") (name "VCC") (class "Default")
      (node (ref "C010") (pin "1") (pinfunction "1_1") (pintype "passive"))
      (node (ref "C418") (pin "2") (pinfunction "2_2") (pintype "passive"))
      (node (ref "D501") (pin "A") (pinfunction "A_A") (pintype "passive"))
      (node (ref "D502") (pin "A") (pinfunction "A_A") (pintype "passive"))
      (node (ref "J001") (pin "3") (pinfunction "3_3") (pintype "passive"))
      (node (ref "J002") (pin "3") (pinfunction "3_3") (pintype "passive"))
      (node (ref "J003") (pin "2") (pinfunction "2_2") (pintype "passive"))
      (node (ref "J005") (pin "2") (pinfunction "2_2") (pintype "passive"))
      (node (ref "R606") (pin "1") (pinfunction "1_1") (pintype "passive"))
      (node (ref "R606") (pin "4") (pinfunction "1_4") (pintype "passive"))
      (node (ref "U401") (pin "18") (pinfunction "AVCC_18") (pintype "bidirectional"))
      (node (ref "U401") (pin "4") (pinfunction "VCC_4") (pintype "bidirectional"))
      (node (ref "U401") (pin "6") (pinfunction "VCC_6") (pintype "bidirectional"))
      (node (ref "U501") (pin "20") (pinfunction "VCC_20") (pintype "power_in"))
      (node (ref "U501") (pin "4") (pinfunction "VCCIO_4") (pintype "power_in"))
      (node (ref "U602") (pin "5") (pinfunction "VCC_5") (pintype "bidirectional"))
    )
    (net (code "53") (name "unconnected-(D200-PadA)") (class "Default")
      (node (ref "D200") (pin "A") (pinfunction "A_A") (pintype "passive"))
    )
    (net (code "54") (name "unconnected-(D200-PadC)") (class "Default")
      (node (ref "D200") (pin "C") (pinfunction "C_C") (pintype "passive"))
    )
    (net (code "55") (name "unconnected-(D201-PadA)") (class "Default")
      (node (ref "D201") (pin "A") (pinfunction "A_A") (pintype "passive"))
    )
    (net (code "56") (name "unconnected-(D201-PadC)") (class "Default")
      (node (ref "D201") (pin "C") (pinfunction "C_C") (pintype "passive"))
    )
    (net (code "57") (name "unconnected-(D202-PadA)") (class "Default")
      (node (ref "D202") (pin "A") (pinfunction "A_A") (pintype "passive"))
    )
    (net (code "58") (name "unconnected-(D202-PadC)") (class "Default")
      (node (ref "D202") (pin "C") (pinfunction "C_C") (pintype "passive"))
    )
    (net (code "59") (name "unconnected-(D203-PadA)") (class "Default")
      (node (ref "D203") (pin "A") (pinfunction "A_A") (pintype "passive"))
    )
    (net (code "60") (name "unconnected-(D203-PadC)") (class "Default")
      (node (ref "D203") (pin "C") (pinfunction "C_C") (pintype "passive"))
    )
    (net (code "61") (name "unconnected-(D204-PadA)") (class "Default")
      (node (ref "D204") (pin "A") (pinfunction "A_A") (pintype "passive"))
    )
    (net (code "62") (name "unconnected-(D204-PadC)") (class "Default")
      (node (ref "D204") (pin "C") (pinfunction "C_C") (pintype "passive"))
    )
    (net (code "63") (name "unconnected-(D205-PadA)") (class "Default")
      (node (ref "D205") (pin "A") (pinfunction "A_A") (pintype "passive"))
    )
    (net (code "64") (name "unconnected-(D205-PadC)") (class "Default")
      (node (ref "D205") (pin "C") (pinfunction "C_C") (pintype "passive"))
    )
    (net (code "65") (name "unconnected-(D206-PadA)") (class "Default")
      (node (ref "D206") (pin "A") (pinfunction "A_A") (pintype "passive"))
    )
    (net (code "66") (name "unconnected-(D206-PadC)") (class "Default")
      (node (ref "D206") (pin "C") (pinfunction "C_C") (pintype "passive"))
    )
    (net (code "67") (name "unconnected-(D207-PadA)") (class "Default")
      (node (ref "D207") (pin "A") (pinfunction "A_A") (pintype "passive"))
    )
    (net (code "68") (name "unconnected-(D207-PadC)") (class "Default")
      (node (ref "D207") (pin "C") (pinfunction "C_C") (pintype "passive"))
    )
    (net (code "69") (name "unconnected-(D208-PadA)") (class "Default")
      (node (ref "D208") (pin "A") (pinfunction "A_A") (pintype "passive"))
    )
    (net (code "70") (name "unconnected-(D208-PadC)") (class "Default")
      (node (ref "D208") (pin "C") (pinfunction "C_C") (pintype "passive"))
    )
    (net (code "71") (name "unconnected-(D209-PadA)") (class "Default")
      (node (ref "D209") (pin "A") (pinfunction "A_A") (pintype "passive"))
    )
    (net (code "72") (name "unconnected-(D209-PadC)") (class "Default")
      (node (ref "D209") (pin "C") (pinfunction "C_C") (pintype "passive"))
    )
    (net (code "73") (name "unconnected-(D210-PadA)") (class "Default")
      (node (ref "D210") (pin "A") (pinfunction "A_A") (pintype "passive"))
    )
    (net (code "74") (name "unconnected-(D210-PadC)") (class "Default")
      (node (ref "D210") (pin "C") (pinfunction "C_C") (pintype "passive"))
    )
    (net (code "75") (name "unconnected-(D211-PadA)") (class "Default")
      (node (ref "D211") (pin "A") (pinfunction "A_A") (pintype "passive"))
    )
    (net (code "76") (name "unconnected-(D211-PadC)") (class "Default")
      (node (ref "D211") (pin "C") (pinfunction "C_C") (pintype "passive"))
    )
    (net (code "77") (name "unconnected-(D212-PadA)") (class "Default")
      (node (ref "D212") (pin "A") (pinfunction "A_A") (pintype "passive"))
    )
    (net (code "78") (name "unconnected-(D212-PadC)") (class "Default")
      (node (ref "D212") (pin "C") (pinfunction "C_C") (pintype "passive"))
    )
    (net (code "79") (name "unconnected-(D213-PadA)") (class "Default")
      (node (ref "D213") (pin "A") (pinfunction "A_A") (pintype "passive"))
    )
    (net (code "80") (name "unconnected-(D213-PadC)") (class "Default")
      (node (ref "D213") (pin "C") (pinfunction "C_C") (pintype "passive"))
    )
    (net (code "81") (name "unconnected-(D214-PadA)") (class "Default")
      (node (ref "D214") (pin "A") (pinfunction "A_A") (pintype "passive"))
    )
    (net (code "82") (name "unconnected-(D214-PadC)") (class "Default")
      (node (ref "D214") (pin "C") (pinfunction "C_C") (pintype "passive"))
    )
    (net (code "83") (name "unconnected-(D215-PadA)") (class "Default")
      (node (ref "D215") (pin "A") (pinfunction "A_A") (pintype "passive"))
    )
    (net (code "84") (name "unconnected-(D215-PadC)") (class "Default")
      (node (ref "D215") (pin "C") (pinfunction "C_C") (pintype "passive"))
    )
    (net (code "85") (name "unconnected-(D216-PadA)") (class "Default")
      (node (ref "D216") (pin "A") (pinfunction "A_A") (pintype "passive"))
    )
    (net (code "86") (name "unconnected-(D216-PadC)") (class "Default")
      (node (ref "D216") (pin "C") (pinfunction "C_C") (pintype "passive"))
    )
    (net (code "87") (name "unconnected-(D217-PadA)") (class "Default")
      (node (ref "D217") (pin "A") (pinfunction "A_A") (pintype "passive"))
    )
    (net (code "88") (name "unconnected-(D217-PadC)") (class "Default")
      (node (ref "D217") (pin "C") (pinfunction "C_C") (pintype "passive"))
    )
    (net (code "89") (name "unconnected-(D218-PadA)") (class "Default")
      (node (ref "D218") (pin "A") (pinfunction "A_A") (pintype "passive"))
    )
    (net (code "90") (name "unconnected-(D218-PadC)") (class "Default")
      (node (ref "D218") (pin "C") (pinfunction "C_C") (pintype "passive"))
    )
    (net (code "91") (name "unconnected-(D219-PadA)") (class "Default")
      (node (ref "D219") (pin "A") (pinfunction "A_A") (pintype "passive"))
    )
    (net (code "92") (name "unconnected-(D219-PadC)") (class "Default")
      (node (ref "D219") (pin "C") (pinfunction "C_C") (pintype "passive"))
    )
    (net (code "93") (name "unconnected-(D220-PadA)") (class "Default")
      (node (ref "D220") (pin "A") (pinfunction "A_A") (pintype "passive"))
    )
    (net (code "94") (name "unconnected-(D220-PadC)") (class "Default")
      (node (ref "D220") (pin "C") (pinfunction "C_C") (pintype "passive"))
    )
    (net (code "95") (name "unconnected-(D221-PadA)") (class "Default")
      (node (ref "D221") (pin "A") (pinfunction "A_A") (pintype "passive"))
    )
    (net (code "96") (name "unconnected-(D221-PadC)") (class "Default")
      (node (ref "D221") (pin "C") (pinfunction "C_C") (pintype "passive"))
    )
    (net (code "97") (name "unconnected-(D222-PadA)") (class "Default")
      (node (ref "D222") (pin "A") (pinfunction "A_A") (pintype "passive"))
    )
    (net (code "98") (name "unconnected-(D222-PadC)") (class "Default")
      (node (ref "D222") (pin "C") (pinfunction "C_C") (pintype "passive"))
    )
    (net (code "99") (name "unconnected-(D223-PadA)") (class "Default")
      (node (ref "D223") (pin "A") (pinfunction "A_A") (pintype "passive"))
    )
    (net (code "100") (name "unconnected-(D223-PadC)") (class "Default")
      (node (ref "D223") (pin "C") (pinfunction "C_C") (pintype "passive"))
    )
    (net (code "101") (name "unconnected-(D224-PadA)") (class "Default")
      (node (ref "D224") (pin "A") (pinfunction "A_A") (pintype "passive"))
    )
    (net (code "102") (name "unconnected-(D224-PadC)") (class "Default")
      (node (ref "D224") (pin "C") (pinfunction "C_C") (pintype "passive"))
    )
    (net (code "103") (name "unconnected-(D225-PadA)") (class "Default")
      (node (ref "D225") (pin "A") (pinfunction "A_A") (pintype "passive"))
    )
    (net (code "104") (name "unconnected-(D225-PadC)") (class "Default")
      (node (ref "D225") (pin "C") (pinfunction "C_C") (pintype "passive"))
    )
    (net (code "105") (name "unconnected-(D226-PadA)") (class "Default")
      (node (ref "D226") (pin "A") (pinfunction "A_A") (pintype "passive"))
    )
    (net (code "106") (name "unconnected-(D226-PadC)") (class "Default")
      (node (ref "D226") (pin "C") (pinfunction "C_C") (pintype "passive"))
    )
    (net (code "107") (name "unconnected-(D227-PadA)") (class "Default")
      (node (ref "D227") (pin "A") (pinfunction "A_A") (pintype "passive"))
    )
    (net (code "108") (name "unconnected-(D227-PadC)") (class "Default")
      (node (ref "D227") (pin "C") (pinfunction "C_C") (pintype "passive"))
    )
    (net (code "109") (name "unconnected-(D228-PadA)") (class "Default")
      (node (ref "D228") (pin "A") (pinfunction "A_A") (pintype "passive"))
    )
    (net (code "110") (name "unconnected-(D228-PadC)") (class "Default")
      (node (ref "D228") (pin "C") (pinfunction "C_C") (pintype "passive"))
    )
    (net (code "111") (name "unconnected-(D229-PadA)") (class "Default")
      (node (ref "D229") (pin "A") (pinfunction "A_A") (pintype "passive"))
    )
    (net (code "112") (name "unconnected-(D229-PadC)") (class "Default")
      (node (ref "D229") (pin "C") (pinfunction "C_C") (pintype "passive"))
    )
    (net (code "113") (name "unconnected-(D230-PadA)") (class "Default")
      (node (ref "D230") (pin "A") (pinfunction "A_A") (pintype "passive"))
    )
    (net (code "114") (name "unconnected-(D230-PadC)") (class "Default")
      (node (ref "D230") (pin "C") (pinfunction "C_C") (pintype "passive"))
    )
    (net (code "115") (name "unconnected-(D231-PadA)") (class "Default")
      (node (ref "D231") (pin "A") (pinfunction "A_A") (pintype "passive"))
    )
    (net (code "116") (name "unconnected-(D231-PadC)") (class "Default")
      (node (ref "D231") (pin "C") (pinfunction "C_C") (pintype "passive"))
    )
    (net (code "117") (name "unconnected-(D232-PadA)") (class "Default")
      (node (ref "D232") (pin "A") (pinfunction "A_A") (pintype "passive"))
    )
    (net (code "118") (name "unconnected-(D232-PadC)") (class "Default")
      (node (ref "D232") (pin "C") (pinfunction "C_C") (pintype "passive"))
    )
    (net (code "119") (name "unconnected-(D233-PadA)") (class "Default")
      (node (ref "D233") (pin "A") (pinfunction "A_A") (pintype "passive"))
    )
    (net (code "120") (name "unconnected-(D233-PadC)") (class "Default")
      (node (ref "D233") (pin "C") (pinfunction "C_C") (pintype "passive"))
    )
    (net (code "121") (name "unconnected-(D234-PadA)") (class "Default")
      (node (ref "D234") (pin "A") (pinfunction "A_A") (pintype "passive"))
    )
    (net (code "122") (name "unconnected-(D234-PadC)") (class "Default")
      (node (ref "D234") (pin "C") (pinfunction "C_C") (pintype "passive"))
    )
    (net (code "123") (name "unconnected-(D235-PadA)") (class "Default")
      (node (ref "D235") (pin "A") (pinfunction "A_A") (pintype "passive"))
    )
    (net (code "124") (name "unconnected-(D235-PadC)") (class "Default")
      (node (ref "D235") (pin "C") (pinfunction "C_C") (pintype "passive"))
    )
    (net (code "125") (name "unconnected-(D236-PadA)") (class "Default")
      (node (ref "D236") (pin "A") (pinfunction "A_A") (pintype "passive"))
    )
    (net (code "126") (name "unconnected-(D236-PadC)") (class "Default")
      (node (ref "D236") (pin "C") (pinfunction "C_C") (pintype "passive"))
    )
    (net (code "127") (name "unconnected-(D237-PadA)") (class "Default")
      (node (ref "D237") (pin "A") (pinfunction "A_A") (pintype "passive"))
    )
    (net (code "128") (name "unconnected-(D237-PadC)") (class "Default")
      (node (ref "D237") (pin "C") (pinfunction "C_C") (pintype "passive"))
    )
    (net (code "129") (name "unconnected-(D238-PadA)") (class "Default")
      (node (ref "D238") (pin "A") (pinfunction "A_A") (pintype "passive"))
    )
    (net (code "130") (name "unconnected-(D238-PadC)") (class "Default")
      (node (ref "D238") (pin "C") (pinfunction "C_C") (pintype "passive"))
    )
    (net (code "131") (name "unconnected-(D239-PadA)") (class "Default")
      (node (ref "D239") (pin "A") (pinfunction "A_A") (pintype "passive"))
    )
    (net (code "132") (name "unconnected-(D239-PadC)") (class "Default")
      (node (ref "D239") (pin "C") (pinfunction "C_C") (pintype "passive"))
    )
    (net (code "133") (name "unconnected-(D240-PadA)") (class "Default")
      (node (ref "D240") (pin "A") (pinfunction "A_A") (pintype "passive"))
    )
    (net (code "134") (name "unconnected-(D240-PadC)") (class "Default")
      (node (ref "D240") (pin "C") (pinfunction "C_C") (pintype "passive"))
    )
    (net (code "135") (name "unconnected-(D241-PadA)") (class "Default")
      (node (ref "D241") (pin "A") (pinfunction "A_A") (pintype "passive"))
    )
    (net (code "136") (name "unconnected-(D241-PadC)") (class "Default")
      (node (ref "D241") (pin "C") (pinfunction "C_C") (pintype "passive"))
    )
    (net (code "137") (name "unconnected-(D242-PadA)") (class "Default")
      (node (ref "D242") (pin "A") (pinfunction "A_A") (pintype "passive"))
    )
    (net (code "138") (name "unconnected-(D242-PadC)") (class "Default")
      (node (ref "D242") (pin "C") (pinfunction "C_C") (pintype "passive"))
    )
    (net (code "139") (name "unconnected-(D243-PadA)") (class "Default")
      (node (ref "D243") (pin "A") (pinfunction "A_A") (pintype "passive"))
    )
    (net (code "140") (name "unconnected-(D243-PadC)") (class "Default")
      (node (ref "D243") (pin "C") (pinfunction "C_C") (pintype "passive"))
    )
    (net (code "141") (name "unconnected-(D244-PadA)") (class "Default")
      (node (ref "D244") (pin "A") (pinfunction "A_A") (pintype "passive"))
    )
    (net (code "142") (name "unconnected-(D244-PadC)") (class "Default")
      (node (ref "D244") (pin "C") (pinfunction "C_C") (pintype "passive"))
    )
    (net (code "143") (name "unconnected-(D245-PadA)") (class "Default")
      (node (ref "D245") (pin "A") (pinfunction "A_A") (pintype "passive"))
    )
    (net (code "144") (name "unconnected-(D245-PadC)") (class "Default")
      (node (ref "D245") (pin "C") (pinfunction "C_C") (pintype "passive"))
    )
    (net (code "145") (name "unconnected-(D246-PadA)") (class "Default")
      (node (ref "D246") (pin "A") (pinfunction "A_A") (pintype "passive"))
    )
    (net (code "146") (name "unconnected-(D246-PadC)") (class "Default")
      (node (ref "D246") (pin "C") (pinfunction "C_C") (pintype "passive"))
    )
    (net (code "147") (name "unconnected-(D247-PadA)") (class "Default")
      (node (ref "D247") (pin "A") (pinfunction "A_A") (pintype "passive"))
    )
    (net (code "148") (name "unconnected-(D247-PadC)") (class "Default")
      (node (ref "D247") (pin "C") (pinfunction "C_C") (pintype "passive"))
    )
    (net (code "149") (name "unconnected-(D248-PadA)") (class "Default")
      (node (ref "D248") (pin "A") (pinfunction "A_A") (pintype "passive"))
    )
    (net (code "150") (name "unconnected-(D248-PadC)") (class "Default")
      (node (ref "D248") (pin "C") (pinfunction "C_C") (pintype "passive"))
    )
    (net (code "151") (name "unconnected-(D249-PadA)") (class "Default")
      (node (ref "D249") (pin "A") (pinfunction "A_A") (pintype "passive"))
    )
    (net (code "152") (name "unconnected-(D249-PadC)") (class "Default")
      (node (ref "D249") (pin "C") (pinfunction "C_C") (pintype "passive"))
    )
    (net (code "153") (name "unconnected-(D250-PadA)") (class "Default")
      (node (ref "D250") (pin "A") (pinfunction "A_A") (pintype "passive"))
    )
    (net (code "154") (name "unconnected-(D250-PadC)") (class "Default")
      (node (ref "D250") (pin "C") (pinfunction "C_C") (pintype "passive"))
    )
    (net (code "155") (name "unconnected-(D251-PadA)") (class "Default")
      (node (ref "D251") (pin "A") (pinfunction "A_A") (pintype "passive"))
    )
    (net (code "156") (name "unconnected-(D251-PadC)") (class "Default")
      (node (ref "D251") (pin "C") (pinfunction "C_C") (pintype "passive"))
    )
    (net (code "157") (name "unconnected-(D252-PadA)") (class "Default")
      (node (ref "D252") (pin "A") (pinfunction "A_A") (pintype "passive"))
    )
    (net (code "158") (name "unconnected-(D252-PadC)") (class "Default")
      (node (ref "D252") (pin "C") (pinfunction "C_C") (pintype "passive"))
    )
    (net (code "159") (name "unconnected-(D253-PadA)") (class "Default")
      (node (ref "D253") (pin "A") (pinfunction "A_A") (pintype "passive"))
    )
    (net (code "160") (name "unconnected-(D253-PadC)") (class "Default")
      (node (ref "D253") (pin "C") (pinfunction "C_C") (pintype "passive"))
    )
    (net (code "161") (name "unconnected-(D254-PadA)") (class "Default")
      (node (ref "D254") (pin "A") (pinfunction "A_A") (pintype "passive"))
    )
    (net (code "162") (name "unconnected-(D254-PadC)") (class "Default")
      (node (ref "D254") (pin "C") (pinfunction "C_C") (pintype "passive"))
    )
    (net (code "163") (name "unconnected-(D255-PadA)") (class "Default")
      (node (ref "D255") (pin "A") (pinfunction "A_A") (pintype "passive"))
    )
    (net (code "164") (name "unconnected-(D255-PadC)") (class "Default")
      (node (ref "D255") (pin "C") (pinfunction "C_C") (pintype "passive"))
    )
    (net (code "165") (name "unconnected-(D256-PadA)") (class "Default")
      (node (ref "D256") (pin "A") (pinfunction "A_A") (pintype "passive"))
    )
    (net (code "166") (name "unconnected-(D256-PadC)") (class "Default")
      (node (ref "D256") (pin "C") (pinfunction "C_C") (pintype "passive"))
    )
    (net (code "167") (name "unconnected-(D257-PadA)") (class "Default")
      (node (ref "D257") (pin "A") (pinfunction "A_A") (pintype "passive"))
    )
    (net (code "168") (name "unconnected-(D257-PadC)") (class "Default")
      (node (ref "D257") (pin "C") (pinfunction "C_C") (pintype "passive"))
    )
    (net (code "169") (name "unconnected-(D258-PadA)") (class "Default")
      (node (ref "D258") (pin "A") (pinfunction "A_A") (pintype "passive"))
    )
    (net (code "170") (name "unconnected-(D258-PadC)") (class "Default")
      (node (ref "D258") (pin "C") (pinfunction "C_C") (pintype "passive"))
    )
    (net (code "171") (name "unconnected-(D259-PadA)") (class "Default")
      (node (ref "D259") (pin "A") (pinfunction "A_A") (pintype "passive"))
    )
    (net (code "172") (name "unconnected-(D259-PadC)") (class "Default")
      (node (ref "D259") (pin "C") (pinfunction "C_C") (pintype "passive"))
    )
    (net (code "173") (name "unconnected-(D300-PadA)") (class "Default")
      (node (ref "D300") (pin "A") (pinfunction "A_A") (pintype "passive"))
    )
    (net (code "174") (name "unconnected-(D300-PadC)") (class "Default")
      (node (ref "D300") (pin "C") (pinfunction "C_C") (pintype "passive"))
    )
    (net (code "175") (name "unconnected-(D301-PadA)") (class "Default")
      (node (ref "D301") (pin "A") (pinfunction "A_A") (pintype "passive"))
    )
    (net (code "176") (name "unconnected-(D301-PadC)") (class "Default")
      (node (ref "D301") (pin "C") (pinfunction "C_C") (pintype "passive"))
    )
    (net (code "177") (name "unconnected-(D302-PadA)") (class "Default")
      (node (ref "D302") (pin "A") (pinfunction "A_A") (pintype "passive"))
    )
    (net (code "178") (name "unconnected-(D302-PadC)") (class "Default")
      (node (ref "D302") (pin "C") (pinfunction "C_C") (pintype "passive"))
    )
    (net (code "179") (name "unconnected-(D303-PadA)") (class "Default")
      (node (ref "D303") (pin "A") (pinfunction "A_A") (pintype "passive"))
    )
    (net (code "180") (name "unconnected-(D303-PadC)") (class "Default")
      (node (ref "D303") (pin "C") (pinfunction "C_C") (pintype "passive"))
    )
    (net (code "181") (name "unconnected-(D304-PadA)") (class "Default")
      (node (ref "D304") (pin "A") (pinfunction "A_A") (pintype "passive"))
    )
    (net (code "182") (name "unconnected-(D304-PadC)") (class "Default")
      (node (ref "D304") (pin "C") (pinfunction "C_C") (pintype "passive"))
    )
    (net (code "183") (name "unconnected-(D305-PadA)") (class "Default")
      (node (ref "D305") (pin "A") (pinfunction "A_A") (pintype "passive"))
    )
    (net (code "184") (name "unconnected-(D305-PadC)") (class "Default")
      (node (ref "D305") (pin "C") (pinfunction "C_C") (pintype "passive"))
    )
    (net (code "185") (name "unconnected-(D306-PadA)") (class "Default")
      (node (ref "D306") (pin "A") (pinfunction "A_A") (pintype "passive"))
    )
    (net (code "186") (name "unconnected-(D306-PadC)") (class "Default")
      (node (ref "D306") (pin "C") (pinfunction "C_C") (pintype "passive"))
    )
    (net (code "187") (name "unconnected-(D307-PadA)") (class "Default")
      (node (ref "D307") (pin "A") (pinfunction "A_A") (pintype "passive"))
    )
    (net (code "188") (name "unconnected-(D307-PadC)") (class "Default")
      (node (ref "D307") (pin "C") (pinfunction "C_C") (pintype "passive"))
    )
    (net (code "189") (name "unconnected-(D308-PadA)") (class "Default")
      (node (ref "D308") (pin "A") (pinfunction "A_A") (pintype "passive"))
    )
    (net (code "190") (name "unconnected-(D308-PadC)") (class "Default")
      (node (ref "D308") (pin "C") (pinfunction "C_C") (pintype "passive"))
    )
    (net (code "191") (name "unconnected-(D309-PadA)") (class "Default")
      (node (ref "D309") (pin "A") (pinfunction "A_A") (pintype "passive"))
    )
    (net (code "192") (name "unconnected-(D309-PadC)") (class "Default")
      (node (ref "D309") (pin "C") (pinfunction "C_C") (pintype "passive"))
    )
    (net (code "193") (name "unconnected-(D310-PadA)") (class "Default")
      (node (ref "D310") (pin "A") (pinfunction "A_A") (pintype "passive"))
    )
    (net (code "194") (name "unconnected-(D310-PadC)") (class "Default")
      (node (ref "D310") (pin "C") (pinfunction "C_C") (pintype "passive"))
    )
    (net (code "195") (name "unconnected-(D311-PadA)") (class "Default")
      (node (ref "D311") (pin "A") (pinfunction "A_A") (pintype "passive"))
    )
    (net (code "196") (name "unconnected-(D311-PadC)") (class "Default")
      (node (ref "D311") (pin "C") (pinfunction "C_C") (pintype "passive"))
    )
    (net (code "197") (name "unconnected-(D312-PadA)") (class "Default")
      (node (ref "D312") (pin "A") (pinfunction "A_A") (pintype "passive"))
    )
    (net (code "198") (name "unconnected-(D312-PadC)") (class "Default")
      (node (ref "D312") (pin "C") (pinfunction "C_C") (pintype "passive"))
    )
    (net (code "199") (name "unconnected-(D313-PadA)") (class "Default")
      (node (ref "D313") (pin "A") (pinfunction "A_A") (pintype "passive"))
    )
    (net (code "200") (name "unconnected-(D313-PadC)") (class "Default")
      (node (ref "D313") (pin "C") (pinfunction "C_C") (pintype "passive"))
    )
    (net (code "201") (name "unconnected-(D314-PadA)") (class "Default")
      (node (ref "D314") (pin "A") (pinfunction "A_A") (pintype "passive"))
    )
    (net (code "202") (name "unconnected-(D314-PadC)") (class "Default")
      (node (ref "D314") (pin "C") (pinfunction "C_C") (pintype "passive"))
    )
    (net (code "203") (name "unconnected-(D315-PadA)") (class "Default")
      (node (ref "D315") (pin "A") (pinfunction "A_A") (pintype "passive"))
    )
    (net (code "204") (name "unconnected-(D315-PadC)") (class "Default")
      (node (ref "D315") (pin "C") (pinfunction "C_C") (pintype "passive"))
    )
    (net (code "205") (name "unconnected-(D316-PadA)") (class "Default")
      (node (ref "D316") (pin "A") (pinfunction "A_A") (pintype "passive"))
    )
    (net (code "206") (name "unconnected-(D316-PadC)") (class "Default")
      (node (ref "D316") (pin "C") (pinfunction "C_C") (pintype "passive"))
    )
    (net (code "207") (name "unconnected-(D317-PadA)") (class "Default")
      (node (ref "D317") (pin "A") (pinfunction "A_A") (pintype "passive"))
    )
    (net (code "208") (name "unconnected-(D317-PadC)") (class "Default")
      (node (ref "D317") (pin "C") (pinfunction "C_C") (pintype "passive"))
    )
    (net (code "209") (name "unconnected-(D318-PadA)") (class "Default")
      (node (ref "D318") (pin "A") (pinfunction "A_A") (pintype "passive"))
    )
    (net (code "210") (name "unconnected-(D318-PadC)") (class "Default")
      (node (ref "D318") (pin "C") (pinfunction "C_C") (pintype "passive"))
    )
    (net (code "211") (name "unconnected-(D319-PadA)") (class "Default")
      (node (ref "D319") (pin "A") (pinfunction "A_A") (pintype "passive"))
    )
    (net (code "212") (name "unconnected-(D319-PadC)") (class "Default")
      (node (ref "D319") (pin "C") (pinfunction "C_C") (pintype "passive"))
    )
    (net (code "213") (name "unconnected-(D320-PadA)") (class "Default")
      (node (ref "D320") (pin "A") (pinfunction "A_A") (pintype "passive"))
    )
    (net (code "214") (name "unconnected-(D320-PadC)") (class "Default")
      (node (ref "D320") (pin "C") (pinfunction "C_C") (pintype "passive"))
    )
    (net (code "215") (name "unconnected-(D321-PadA)") (class "Default")
      (node (ref "D321") (pin "A") (pinfunction "A_A") (pintype "passive"))
    )
    (net (code "216") (name "unconnected-(D321-PadC)") (class "Default")
      (node (ref "D321") (pin "C") (pinfunction "C_C") (pintype "passive"))
    )
    (net (code "217") (name "unconnected-(D322-PadA)") (class "Default")
      (node (ref "D322") (pin "A") (pinfunction "A_A") (pintype "passive"))
    )
    (net (code "218") (name "unconnected-(D322-PadC)") (class "Default")
      (node (ref "D322") (pin "C") (pinfunction "C_C") (pintype "passive"))
    )
    (net (code "219") (name "unconnected-(D323-PadA)") (class "Default")
      (node (ref "D323") (pin "A") (pinfunction "A_A") (pintype "passive"))
    )
    (net (code "220") (name "unconnected-(D323-PadC)") (class "Default")
      (node (ref "D323") (pin "C") (pinfunction "C_C") (pintype "passive"))
    )
    (net (code "221") (name "unconnected-(D324-PadA)") (class "Default")
      (node (ref "D324") (pin "A") (pinfunction "A_A") (pintype "passive"))
    )
    (net (code "222") (name "unconnected-(D324-PadC)") (class "Default")
      (node (ref "D324") (pin "C") (pinfunction "C_C") (pintype "passive"))
    )
    (net (code "223") (name "unconnected-(D325-PadA)") (class "Default")
      (node (ref "D325") (pin "A") (pinfunction "A_A") (pintype "passive"))
    )
    (net (code "224") (name "unconnected-(D325-PadC)") (class "Default")
      (node (ref "D325") (pin "C") (pinfunction "C_C") (pintype "passive"))
    )
    (net (code "225") (name "unconnected-(D326-PadA)") (class "Default")
      (node (ref "D326") (pin "A") (pinfunction "A_A") (pintype "passive"))
    )
    (net (code "226") (name "unconnected-(D326-PadC)") (class "Default")
      (node (ref "D326") (pin "C") (pinfunction "C_C") (pintype "passive"))
    )
    (net (code "227") (name "unconnected-(D327-PadA)") (class "Default")
      (node (ref "D327") (pin "A") (pinfunction "A_A") (pintype "passive"))
    )
    (net (code "228") (name "unconnected-(D327-PadC)") (class "Default")
      (node (ref "D327") (pin "C") (pinfunction "C_C") (pintype "passive"))
    )
    (net (code "229") (name "unconnected-(D328-PadA)") (class "Default")
      (node (ref "D328") (pin "A") (pinfunction "A_A") (pintype "passive"))
    )
    (net (code "230") (name "unconnected-(D328-PadC)") (class "Default")
      (node (ref "D328") (pin "C") (pinfunction "C_C") (pintype "passive"))
    )
    (net (code "231") (name "unconnected-(D329-PadA)") (class "Default")
      (node (ref "D329") (pin "A") (pinfunction "A_A") (pintype "passive"))
    )
    (net (code "232") (name "unconnected-(D329-PadC)") (class "Default")
      (node (ref "D329") (pin "C") (pinfunction "C_C") (pintype "passive"))
    )
    (net (code "233") (name "unconnected-(D330-PadA)") (class "Default")
      (node (ref "D330") (pin "A") (pinfunction "A_A") (pintype "passive"))
    )
    (net (code "234") (name "unconnected-(D330-PadC)") (class "Default")
      (node (ref "D330") (pin "C") (pinfunction "C_C") (pintype "passive"))
    )
    (net (code "235") (name "unconnected-(D331-PadA)") (class "Default")
      (node (ref "D331") (pin "A") (pinfunction "A_A") (pintype "passive"))
    )
    (net (code "236") (name "unconnected-(D331-PadC)") (class "Default")
      (node (ref "D331") (pin "C") (pinfunction "C_C") (pintype "passive"))
    )
    (net (code "237") (name "unconnected-(D332-PadA)") (class "Default")
      (node (ref "D332") (pin "A") (pinfunction "A_A") (pintype "passive"))
    )
    (net (code "238") (name "unconnected-(D332-PadC)") (class "Default")
      (node (ref "D332") (pin "C") (pinfunction "C_C") (pintype "passive"))
    )
    (net (code "239") (name "unconnected-(D333-PadA)") (class "Default")
      (node (ref "D333") (pin "A") (pinfunction "A_A") (pintype "passive"))
    )
    (net (code "240") (name "unconnected-(D333-PadC)") (class "Default")
      (node (ref "D333") (pin "C") (pinfunction "C_C") (pintype "passive"))
    )
    (net (code "241") (name "unconnected-(D334-PadA)") (class "Default")
      (node (ref "D334") (pin "A") (pinfunction "A_A") (pintype "passive"))
    )
    (net (code "242") (name "unconnected-(D334-PadC)") (class "Default")
      (node (ref "D334") (pin "C") (pinfunction "C_C") (pintype "passive"))
    )
    (net (code "243") (name "unconnected-(D335-PadA)") (class "Default")
      (node (ref "D335") (pin "A") (pinfunction "A_A") (pintype "passive"))
    )
    (net (code "244") (name "unconnected-(D335-PadC)") (class "Default")
      (node (ref "D335") (pin "C") (pinfunction "C_C") (pintype "passive"))
    )
    (net (code "245") (name "unconnected-(D336-PadA)") (class "Default")
      (node (ref "D336") (pin "A") (pinfunction "A_A") (pintype "passive"))
    )
    (net (code "246") (name "unconnected-(D336-PadC)") (class "Default")
      (node (ref "D336") (pin "C") (pinfunction "C_C") (pintype "passive"))
    )
    (net (code "247") (name "unconnected-(D337-PadA)") (class "Default")
      (node (ref "D337") (pin "A") (pinfunction "A_A") (pintype "passive"))
    )
    (net (code "248") (name "unconnected-(D337-PadC)") (class "Default")
      (node (ref "D337") (pin "C") (pinfunction "C_C") (pintype "passive"))
    )
    (net (code "249") (name "unconnected-(D338-PadA)") (class "Default")
      (node (ref "D338") (pin "A") (pinfunction "A_A") (pintype "passive"))
    )
    (net (code "250") (name "unconnected-(D338-PadC)") (class "Default")
      (node (ref "D338") (pin "C") (pinfunction "C_C") (pintype "passive"))
    )
    (net (code "251") (name "unconnected-(D339-PadA)") (class "Default")
      (node (ref "D339") (pin "A") (pinfunction "A_A") (pintype "passive"))
    )
    (net (code "252") (name "unconnected-(D339-PadC)") (class "Default")
      (node (ref "D339") (pin "C") (pinfunction "C_C") (pintype "passive"))
    )
    (net (code "253") (name "unconnected-(D340-PadA)") (class "Default")
      (node (ref "D340") (pin "A") (pinfunction "A_A") (pintype "passive"))
    )
    (net (code "254") (name "unconnected-(D340-PadC)") (class "Default")
      (node (ref "D340") (pin "C") (pinfunction "C_C") (pintype "passive"))
    )
    (net (code "255") (name "unconnected-(D341-PadA)") (class "Default")
      (node (ref "D341") (pin "A") (pinfunction "A_A") (pintype "passive"))
    )
    (net (code "256") (name "unconnected-(D341-PadC)") (class "Default")
      (node (ref "D341") (pin "C") (pinfunction "C_C") (pintype "passive"))
    )
    (net (code "257") (name "unconnected-(D342-PadA)") (class "Default")
      (node (ref "D342") (pin "A") (pinfunction "A_A") (pintype "passive"))
    )
    (net (code "258") (name "unconnected-(D342-PadC)") (class "Default")
      (node (ref "D342") (pin "C") (pinfunction "C_C") (pintype "passive"))
    )
    (net (code "259") (name "unconnected-(D343-PadA)") (class "Default")
      (node (ref "D343") (pin "A") (pinfunction "A_A") (pintype "passive"))
    )
    (net (code "260") (name "unconnected-(D343-PadC)") (class "Default")
      (node (ref "D343") (pin "C") (pinfunction "C_C") (pintype "passive"))
    )
    (net (code "261") (name "unconnected-(D344-PadA)") (class "Default")
      (node (ref "D344") (pin "A") (pinfunction "A_A") (pintype "passive"))
    )
    (net (code "262") (name "unconnected-(D344-PadC)") (class "Default")
      (node (ref "D344") (pin "C") (pinfunction "C_C") (pintype "passive"))
    )
    (net (code "263") (name "unconnected-(D345-PadA)") (class "Default")
      (node (ref "D345") (pin "A") (pinfunction "A_A") (pintype "passive"))
    )
    (net (code "264") (name "unconnected-(D345-PadC)") (class "Default")
      (node (ref "D345") (pin "C") (pinfunction "C_C") (pintype "passive"))
    )
    (net (code "265") (name "unconnected-(D346-PadA)") (class "Default")
      (node (ref "D346") (pin "A") (pinfunction "A_A") (pintype "passive"))
    )
    (net (code "266") (name "unconnected-(D346-PadC)") (class "Default")
      (node (ref "D346") (pin "C") (pinfunction "C_C") (pintype "passive"))
    )
    (net (code "267") (name "unconnected-(D347-PadA)") (class "Default")
      (node (ref "D347") (pin "A") (pinfunction "A_A") (pintype "passive"))
    )
    (net (code "268") (name "unconnected-(D347-PadC)") (class "Default")
      (node (ref "D347") (pin "C") (pinfunction "C_C") (pintype "passive"))
    )
    (net (code "269") (name "unconnected-(D348-PadA)") (class "Default")
      (node (ref "D348") (pin "A") (pinfunction "A_A") (pintype "passive"))
    )
    (net (code "270") (name "unconnected-(D348-PadC)") (class "Default")
      (node (ref "D348") (pin "C") (pinfunction "C_C") (pintype "passive"))
    )
    (net (code "271") (name "unconnected-(D349-PadA)") (class "Default")
      (node (ref "D349") (pin "A") (pinfunction "A_A") (pintype "passive"))
    )
    (net (code "272") (name "unconnected-(D349-PadC)") (class "Default")
      (node (ref "D349") (pin "C") (pinfunction "C_C") (pintype "passive"))
    )
    (net (code "273") (name "unconnected-(D350-PadA)") (class "Default")
      (node (ref "D350") (pin "A") (pinfunction "A_A") (pintype "passive"))
    )
    (net (code "274") (name "unconnected-(D350-PadC)") (class "Default")
      (node (ref "D350") (pin "C") (pinfunction "C_C") (pintype "passive"))
    )
    (net (code "275") (name "unconnected-(D351-PadA)") (class "Default")
      (node (ref "D351") (pin "A") (pinfunction "A_A") (pintype "passive"))
    )
    (net (code "276") (name "unconnected-(D351-PadC)") (class "Default")
      (node (ref "D351") (pin "C") (pinfunction "C_C") (pintype "passive"))
    )
    (net (code "277") (name "unconnected-(D352-PadA)") (class "Default")
      (node (ref "D352") (pin "A") (pinfunction "A_A") (pintype "passive"))
    )
    (net (code "278") (name "unconnected-(D352-PadC)") (class "Default")
      (node (ref "D352") (pin "C") (pinfunction "C_C") (pintype "passive"))
    )
    (net (code "279") (name "unconnected-(D353-PadA)") (class "Default")
      (node (ref "D353") (pin "A") (pinfunction "A_A") (pintype "passive"))
    )
    (net (code "280") (name "unconnected-(D353-PadC)") (class "Default")
      (node (ref "D353") (pin "C") (pinfunction "C_C") (pintype "passive"))
    )
    (net (code "281") (name "unconnected-(D354-PadA)") (class "Default")
      (node (ref "D354") (pin "A") (pinfunction "A_A") (pintype "passive"))
    )
    (net (code "282") (name "unconnected-(D354-PadC)") (class "Default")
      (node (ref "D354") (pin "C") (pinfunction "C_C") (pintype "passive"))
    )
    (net (code "283") (name "unconnected-(D355-PadA)") (class "Default")
      (node (ref "D355") (pin "A") (pinfunction "A_A") (pintype "passive"))
    )
    (net (code "284") (name "unconnected-(D355-PadC)") (class "Default")
      (node (ref "D355") (pin "C") (pinfunction "C_C") (pintype "passive"))
    )
    (net (code "285") (name "unconnected-(D356-PadA)") (class "Default")
      (node (ref "D356") (pin "A") (pinfunction "A_A") (pintype "passive"))
    )
    (net (code "286") (name "unconnected-(D356-PadC)") (class "Default")
      (node (ref "D356") (pin "C") (pinfunction "C_C") (pintype "passive"))
    )
    (net (code "287") (name "unconnected-(D357-PadA)") (class "Default")
      (node (ref "D357") (pin "A") (pinfunction "A_A") (pintype "passive"))
    )
    (net (code "288") (name "unconnected-(D357-PadC)") (class "Default")
      (node (ref "D357") (pin "C") (pinfunction "C_C") (pintype "passive"))
    )
    (net (code "289") (name "unconnected-(D358-PadA)") (class "Default")
      (node (ref "D358") (pin "A") (pinfunction "A_A") (pintype "passive"))
    )
    (net (code "290") (name "unconnected-(D358-PadC)") (class "Default")
      (node (ref "D358") (pin "C") (pinfunction "C_C") (pintype "passive"))
    )
    (net (code "291") (name "unconnected-(D359-PadA)") (class "Default")
      (node (ref "D359") (pin "A") (pinfunction "A_A") (pintype "passive"))
    )
    (net (code "292") (name "unconnected-(D359-PadC)") (class "Default")
      (node (ref "D359") (pin "C") (pinfunction "C_C") (pintype "passive"))
    )
    (net (code "293") (name "unconnected-(U401-ADC6-Pad19)") (class "Default")
      (node (ref "U401") (pin "19") (pinfunction "ADC6_19") (pintype "bidirectional"))
    )
    (net (code "294") (name "unconnected-(U401-ADC7-Pad22)") (class "Default")
      (node (ref "U401") (pin "22") (pinfunction "ADC7_22") (pintype "bidirectional"))
    )
    (net (code "295") (name "unconnected-(U501-CTS-Pad11)") (class "Default")
      (node (ref "U501") (pin "11") (pinfunction "CTS_11") (pintype "input"))
    )
    (net (code "296") (name "unconnected-(U501-DCD-Pad10)") (class "Default")
      (node (ref "U501") (pin "10") (pinfunction "DCD_10") (pintype "input"))
    )
    (net (code "297") (name "unconnected-(U501-DSR-Pad9)") (class "Default")
      (node (ref "U501") (pin "9") (pinfunction "DSR_9") (pintype "input"))
    )
    (net (code "298") (name "unconnected-(U501-OSCI-Pad27)") (class "Default")
      (node (ref "U501") (pin "27") (pinfunction "OSCI_27") (pintype "input"))
    )
    (net (code "299") (name "unconnected-(U501-OSCO-Pad28)") (class "Default")
      (node (ref "U501") (pin "28") (pinfunction "OSCO_28") (pintype "output"))
    )
    (net (code "300") (name "unconnected-(U501-PWREN-Pad14)") (class "Default")
      (node (ref "U501") (pin "14") (pinfunction "PWREN_14") (pintype "input"))
    )
    (net (code "301") (name "unconnected-(U501-RESET-Pad19)") (class "Default")
      (node (ref "U501") (pin "19") (pinfunction "RESET_19") (pintype "input"))
    )
    (net (code "302") (name "unconnected-(U501-RI-Pad6)") (class "Default")
      (node (ref "U501") (pin "6") (pinfunction "RI_6") (pintype "input"))
    )
    (net (code "303") (name "unconnected-(U501-RTS-Pad3)") (class "Default")
      (node (ref "U501") (pin "3") (pinfunction "RTS_3") (pintype "output"))
    )
    (net (code "304") (name "unconnected-(U501-SLEEP-Pad12)") (class "Default")
      (node (ref "U501") (pin "12") (pinfunction "SLEEP_12") (pintype "input"))
    )
    (net (code "305") (name "unconnected-(U501-TXDEN-Pad13)") (class "Default")
      (node (ref "U501") (pin "13") (pinfunction "TXDEN_13") (pintype "input"))
    )
  )
)
